# TempModule.net
KiCad netlist of a schematic drawn in EAGLE
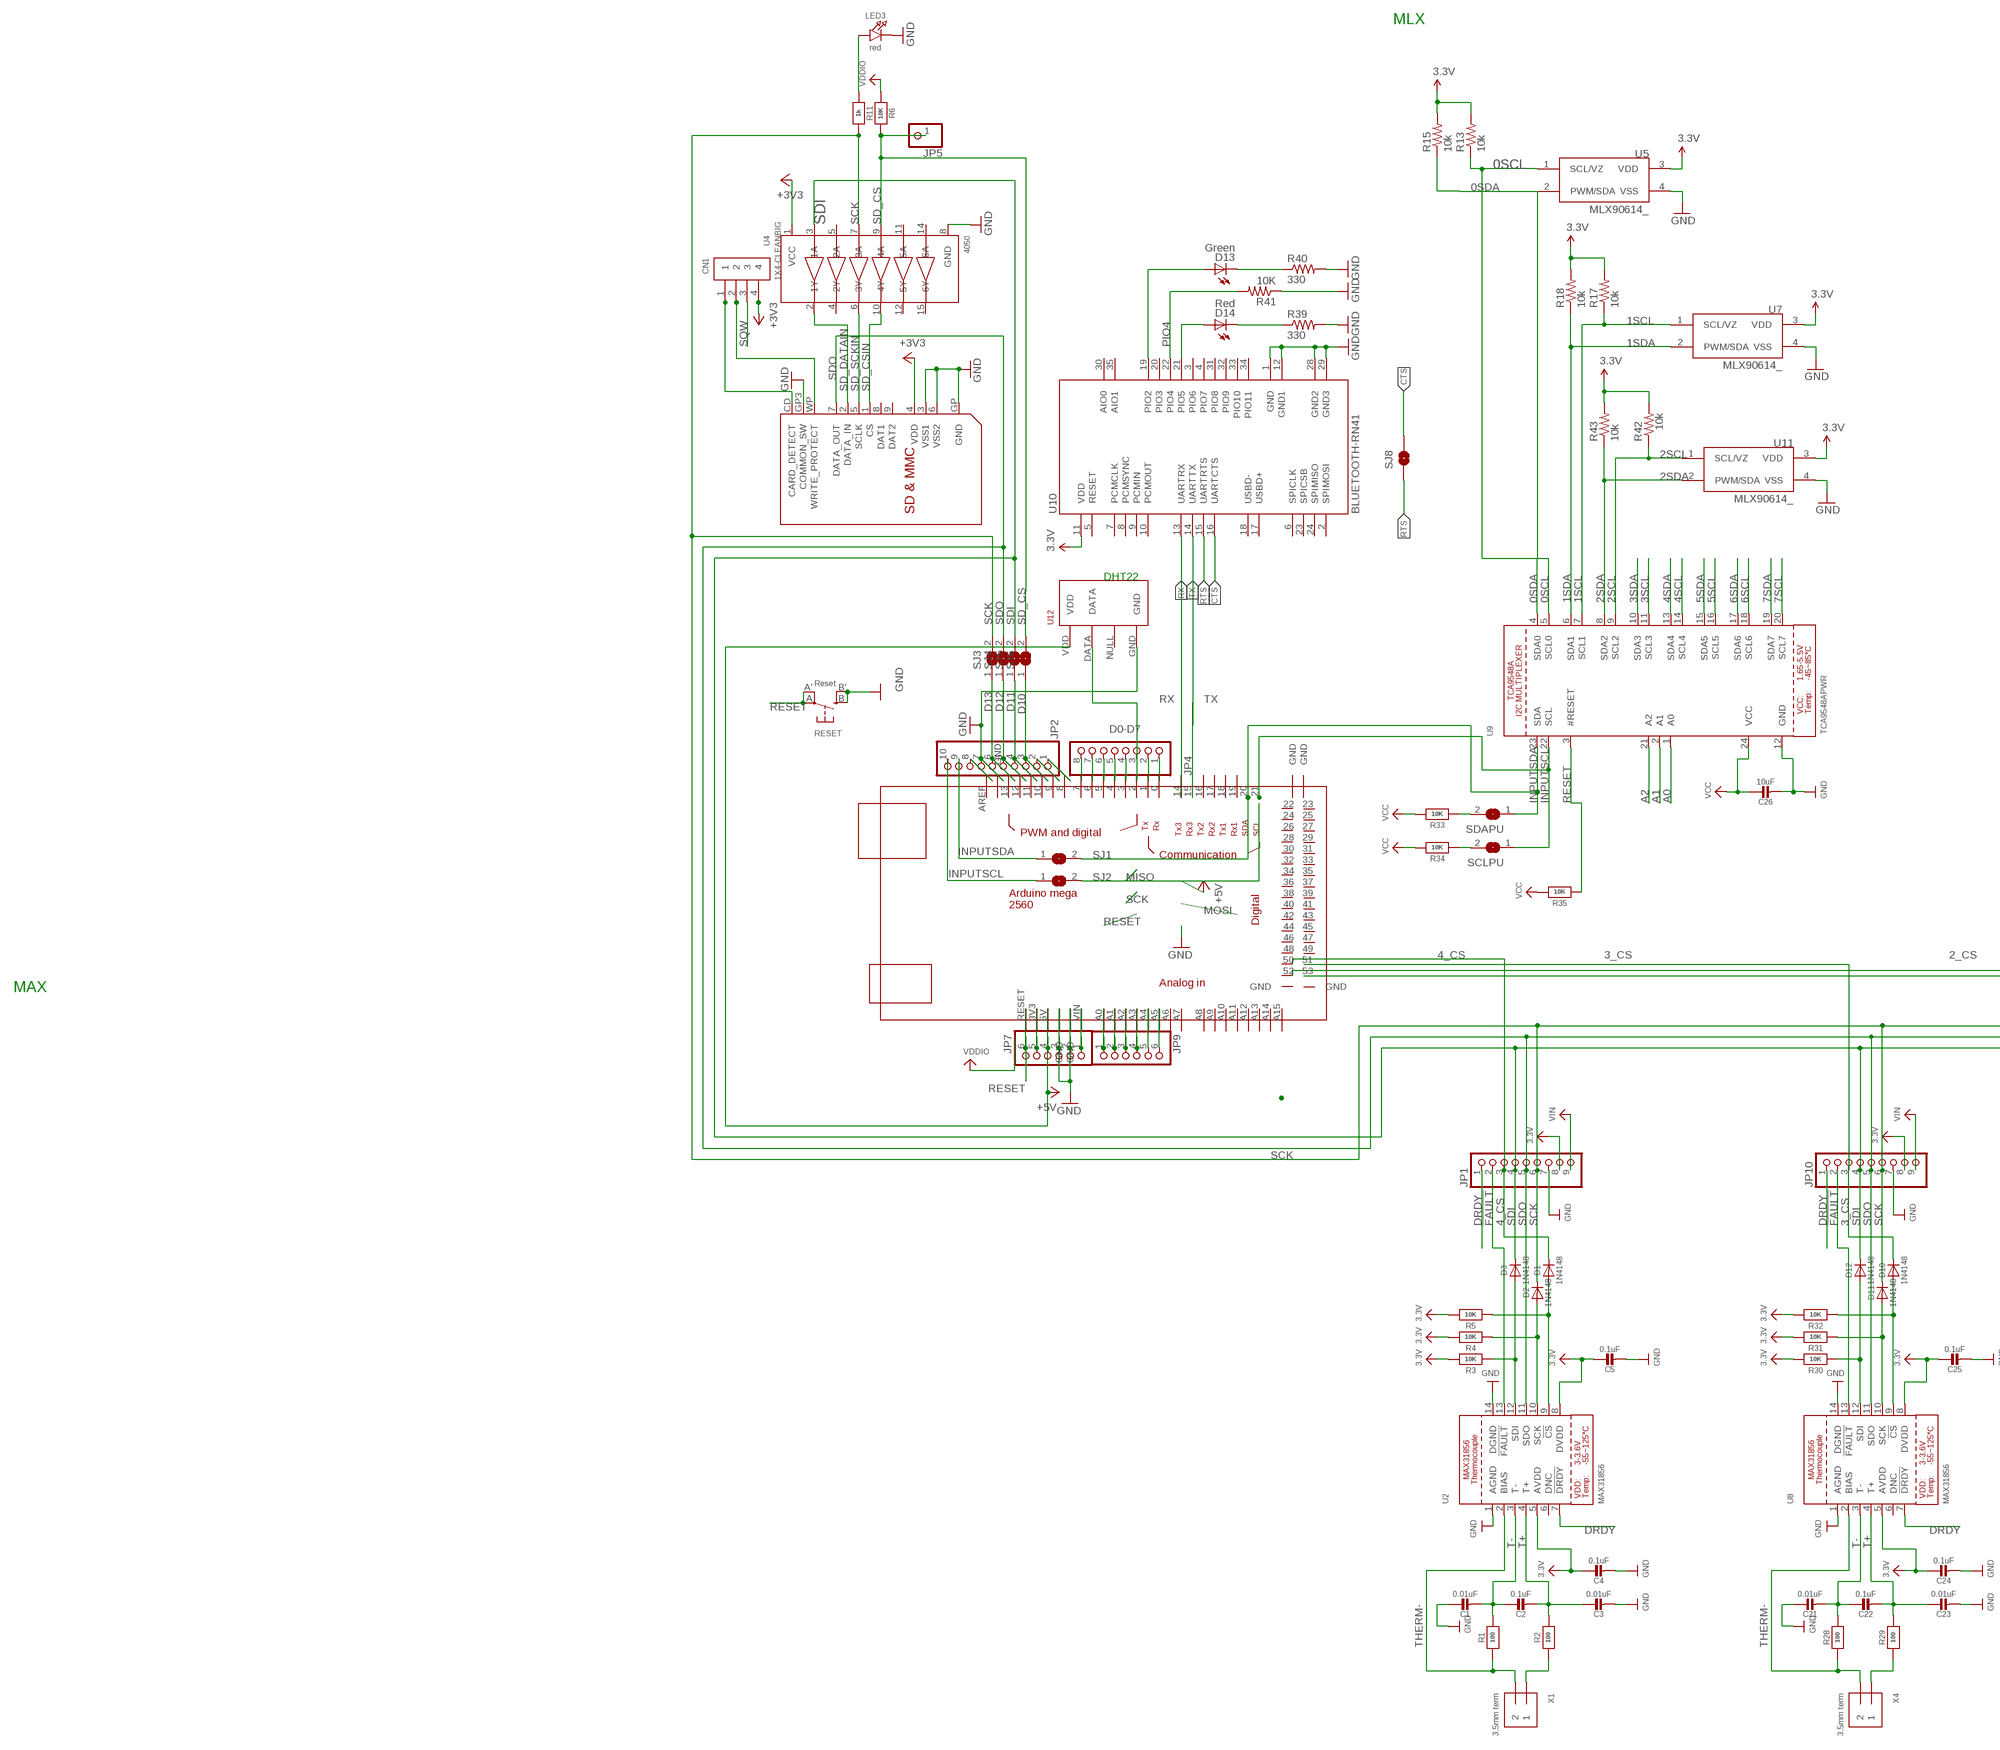
[diagram p0: schematic, sheet 1, part 1 of 2]
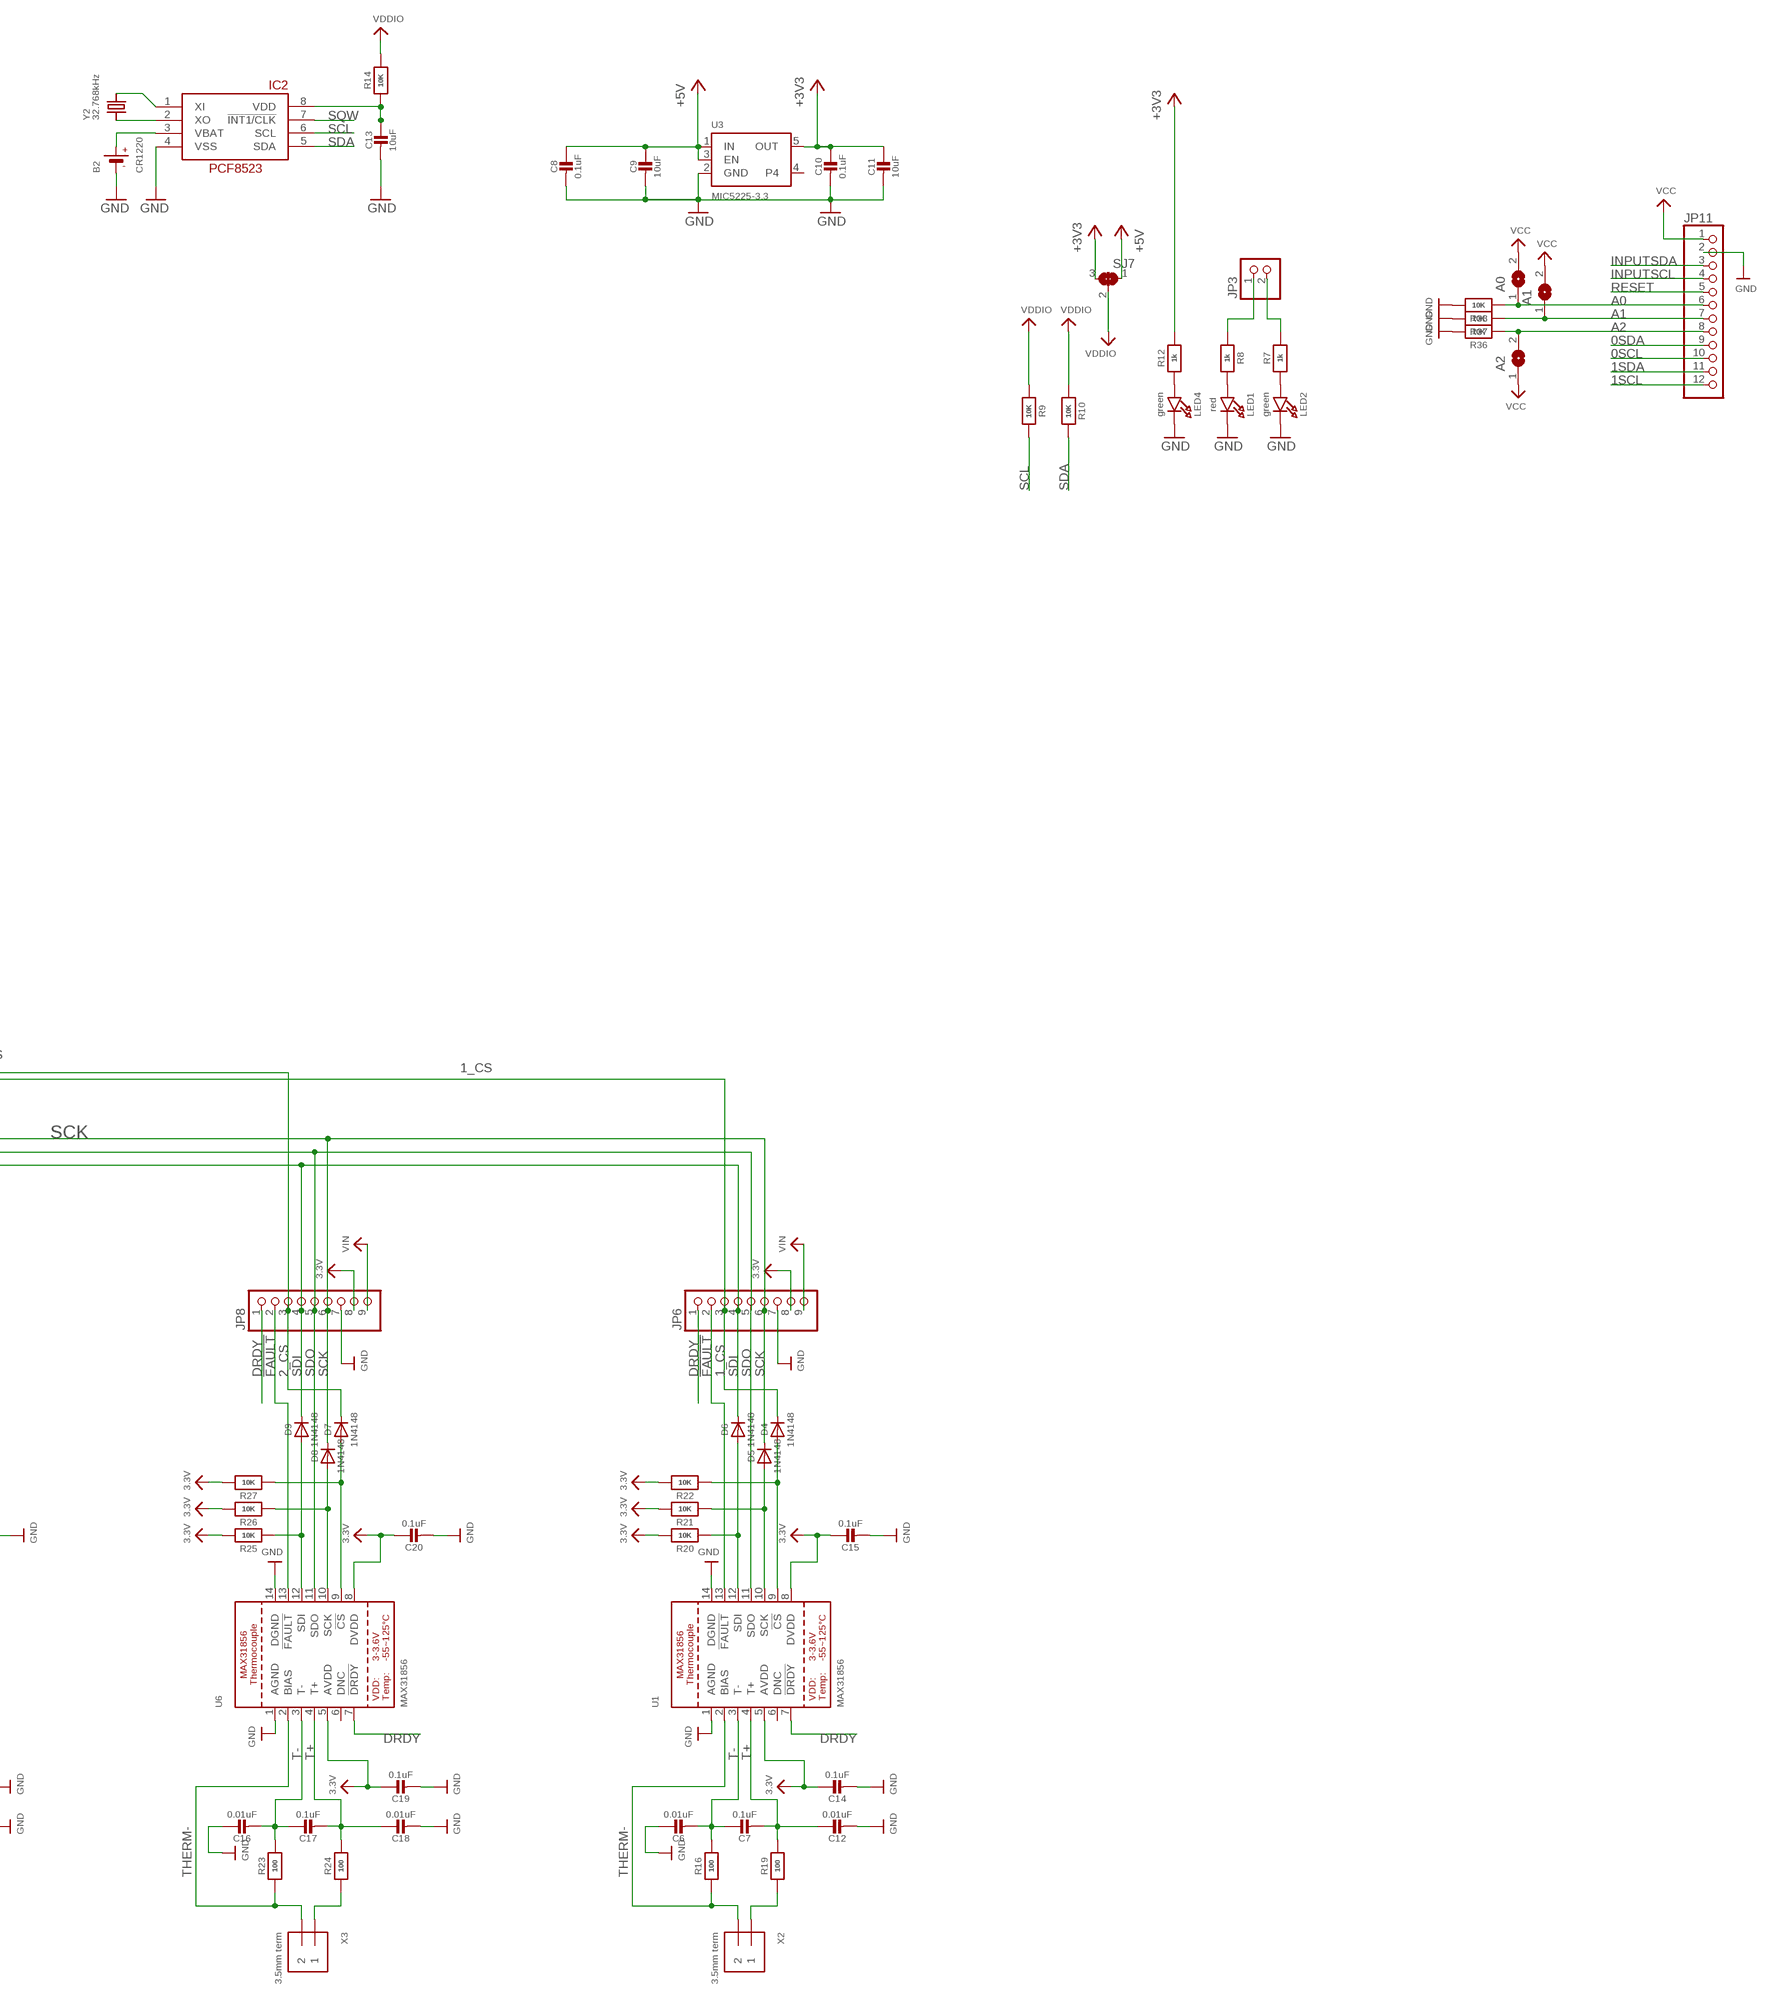
[diagram p1: schematic, sheet 1, part 2 of 2]

(export (version "E")
  (design (tool "Eeschema 10.0.6"))
  (components
    (comp (ref "A0")
      (value "SOLDERJUMPER")
      (footprint "eagle-import:SOLDERJUMPER_ARROW_NOPASTE")
      (libsource (lib "eagle-import") (part "SOLDERJUMPER"))
    )
    (comp (ref "A1")
      (value "SOLDERJUMPER")
      (footprint "eagle-import:SOLDERJUMPER_ARROW_NOPASTE")
      (libsource (lib "eagle-import") (part "SOLDERJUMPER"))
    )
    (comp (ref "A2")
      (value "SOLDERJUMPER")
      (footprint "eagle-import:SOLDERJUMPER_ARROW_NOPASTE")
      (libsource (lib "eagle-import") (part "SOLDERJUMPER"))
    )
    (comp (ref "B2")
      (value "CR1220")
      (footprint "eagle-import:CR1220")
      (libsource (lib "eagle-import") (part "BATTERYCR1220_SMT"))
    )
    (comp (ref "C1")
      (value "0.01uF")
      (footprint "eagle-import:0805_10MGAP")
      (libsource (lib "eagle-import") (part "CAP_CERAMIC0805_10MGAP"))
    )
    (comp (ref "C2")
      (value "0.1uF")
      (footprint "eagle-import:0805-NO")
      (libsource (lib "eagle-import") (part "CAP_CERAMIC0805-NOOUTLINE"))
    )
    (comp (ref "C3")
      (value "0.01uF")
      (footprint "eagle-import:0805-NO")
      (libsource (lib "eagle-import") (part "CAP_CERAMIC0805-NOOUTLINE"))
    )
    (comp (ref "C4")
      (value "0.1uF")
      (footprint "eagle-import:0805-NO")
      (libsource (lib "eagle-import") (part "CAP_CERAMIC0805-NOOUTLINE"))
    )
    (comp (ref "C5")
      (value "0.1uF")
      (footprint "eagle-import:0805-NO")
      (libsource (lib "eagle-import") (part "CAP_CERAMIC0805-NOOUTLINE"))
    )
    (comp (ref "C6")
      (value "0.01uF")
      (footprint "eagle-import:0805_10MGAP")
      (libsource (lib "eagle-import") (part "CAP_CERAMIC0805_10MGAP"))
    )
    (comp (ref "C7")
      (value "0.1uF")
      (footprint "eagle-import:0805-NO")
      (libsource (lib "eagle-import") (part "CAP_CERAMIC0805-NOOUTLINE"))
    )
    (comp (ref "C8")
      (value "0.1uF")
      (footprint "eagle-import:0805-NO")
      (libsource (lib "eagle-import") (part "CAP_CERAMIC0805-NOOUTLINE"))
    )
    (comp (ref "C9")
      (value "10uF")
      (footprint "eagle-import:0805-NO")
      (libsource (lib "eagle-import") (part "CAP_CERAMIC0805-NOOUTLINE"))
    )
    (comp (ref "C10")
      (value "0.1uF")
      (footprint "eagle-import:0805-NO")
      (libsource (lib "eagle-import") (part "CAP_CERAMIC0805-NOOUTLINE"))
    )
    (comp (ref "C11")
      (value "10uF")
      (footprint "eagle-import:0805-NO")
      (libsource (lib "eagle-import") (part "CAP_CERAMIC0805-NOOUTLINE"))
    )
    (comp (ref "C12")
      (value "0.01uF")
      (footprint "eagle-import:0805-NO")
      (libsource (lib "eagle-import") (part "CAP_CERAMIC0805-NOOUTLINE"))
    )
    (comp (ref "C13")
      (value "10uF")
      (footprint "eagle-import:0805-NO")
      (libsource (lib "eagle-import") (part "CAP_CERAMIC0805-NOOUTLINE"))
    )
    (comp (ref "C14")
      (value "0.1uF")
      (footprint "eagle-import:0805-NO")
      (libsource (lib "eagle-import") (part "CAP_CERAMIC0805-NOOUTLINE"))
    )
    (comp (ref "C15")
      (value "0.1uF")
      (footprint "eagle-import:0805-NO")
      (libsource (lib "eagle-import") (part "CAP_CERAMIC0805-NOOUTLINE"))
    )
    (comp (ref "C16")
      (value "0.01uF")
      (footprint "eagle-import:0805_10MGAP")
      (libsource (lib "eagle-import") (part "CAP_CERAMIC0805_10MGAP"))
    )
    (comp (ref "C17")
      (value "0.1uF")
      (footprint "eagle-import:0805-NO")
      (libsource (lib "eagle-import") (part "CAP_CERAMIC0805-NOOUTLINE"))
    )
    (comp (ref "C18")
      (value "0.01uF")
      (footprint "eagle-import:0805-NO")
      (libsource (lib "eagle-import") (part "CAP_CERAMIC0805-NOOUTLINE"))
    )
    (comp (ref "C19")
      (value "0.1uF")
      (footprint "eagle-import:0805-NO")
      (libsource (lib "eagle-import") (part "CAP_CERAMIC0805-NOOUTLINE"))
    )
    (comp (ref "C20")
      (value "0.1uF")
      (footprint "eagle-import:0805-NO")
      (libsource (lib "eagle-import") (part "CAP_CERAMIC0805-NOOUTLINE"))
    )
    (comp (ref "C21")
      (value "0.01uF")
      (footprint "eagle-import:0805_10MGAP")
      (libsource (lib "eagle-import") (part "CAP_CERAMIC0805_10MGAP"))
    )
    (comp (ref "C22")
      (value "0.1uF")
      (footprint "eagle-import:0805-NO")
      (libsource (lib "eagle-import") (part "CAP_CERAMIC0805-NOOUTLINE"))
    )
    (comp (ref "C23")
      (value "0.01uF")
      (footprint "eagle-import:0805-NO")
      (libsource (lib "eagle-import") (part "CAP_CERAMIC0805-NOOUTLINE"))
    )
    (comp (ref "C24")
      (value "0.1uF")
      (footprint "eagle-import:0805-NO")
      (libsource (lib "eagle-import") (part "CAP_CERAMIC0805-NOOUTLINE"))
    )
    (comp (ref "C25")
      (value "0.1uF")
      (footprint "eagle-import:0805-NO")
      (libsource (lib "eagle-import") (part "CAP_CERAMIC0805-NOOUTLINE"))
    )
    (comp (ref "C26")
      (value "10uF")
      (footprint "eagle-import:0805-NO")
      (libsource (lib "eagle-import") (part "CAP_CERAMIC0805-NOOUTLINE"))
    )
    (comp (ref "CN1")
      (value "1X4-CLEANBIG")
      (footprint "eagle-import:1X04-CLEANBIG")
      (libsource (lib "eagle-import") (part "1X4-CLEANBIG"))
    )
    (comp (ref "D1")
      (value "1N4148")
      (footprint "eagle-import:SOD-323")
      (libsource (lib "eagle-import") (part "DIODESOD-323"))
    )
    (comp (ref "D2")
      (value "1N4148")
      (footprint "eagle-import:SOD-323")
      (libsource (lib "eagle-import") (part "DIODESOD-323"))
    )
    (comp (ref "D3")
      (value "1N4148")
      (footprint "eagle-import:SOD-323")
      (libsource (lib "eagle-import") (part "DIODESOD-323"))
    )
    (comp (ref "D4")
      (value "1N4148")
      (footprint "eagle-import:SOD-323")
      (libsource (lib "eagle-import") (part "DIODESOD-323"))
    )
    (comp (ref "D5")
      (value "1N4148")
      (footprint "eagle-import:SOD-323")
      (libsource (lib "eagle-import") (part "DIODESOD-323"))
    )
    (comp (ref "D6")
      (value "1N4148")
      (footprint "eagle-import:SOD-323")
      (libsource (lib "eagle-import") (part "DIODESOD-323"))
    )
    (comp (ref "D7")
      (value "1N4148")
      (footprint "eagle-import:SOD-323")
      (libsource (lib "eagle-import") (part "DIODESOD-323"))
    )
    (comp (ref "D8")
      (value "1N4148")
      (footprint "eagle-import:SOD-323")
      (libsource (lib "eagle-import") (part "DIODESOD-323"))
    )
    (comp (ref "D9")
      (value "1N4148")
      (footprint "eagle-import:SOD-323")
      (libsource (lib "eagle-import") (part "DIODESOD-323"))
    )
    (comp (ref "D10")
      (value "1N4148")
      (footprint "eagle-import:SOD-323")
      (libsource (lib "eagle-import") (part "DIODESOD-323"))
    )
    (comp (ref "D11")
      (value "1N4148")
      (footprint "eagle-import:SOD-323")
      (libsource (lib "eagle-import") (part "DIODESOD-323"))
    )
    (comp (ref "D12")
      (value "1N4148")
      (footprint "eagle-import:SOD-323")
      (libsource (lib "eagle-import") (part "DIODESOD-323"))
    )
    (comp (ref "D13")
      (value "Green")
      (footprint "eagle-import:LED-0603")
      (libsource (lib "eagle-import") (part "LED0603"))
    )
    (comp (ref "D14")
      (value "Red")
      (footprint "eagle-import:LED-0603")
      (libsource (lib "eagle-import") (part "LED0603"))
    )
    (comp (ref "IC2")
      (value "PCF8523T")
      (footprint "eagle-import:SOIC8_150MIL")
      (libsource (lib "eagle-import") (part "RTC_PCF8523T"))
    )
    (comp (ref "JP1")
      (value "HEADER-1X970MIL")
      (footprint "eagle-import:1X09_ROUND_70")
      (libsource (lib "eagle-import") (part "HEADER-1X970MIL"))
    )
    (comp (ref "JP2")
      (value "HEADER-1X1070MIL")
      (footprint "eagle-import:1X10_ROUND70")
      (libsource (lib "eagle-import") (part "HEADER-1X1070MIL"))
    )
    (comp (ref "JP3")
      (value "HEADER-1X2ROUND")
      (footprint "eagle-import:1X02_ROUND")
      (libsource (lib "eagle-import") (part "HEADER-1X2ROUND"))
    )
    (comp (ref "JP4")
      (value "D0-D7")
      (footprint "eagle-import:1X08-BIG")
      (libsource (lib "eagle-import") (part "PINHD-1X8BIG"))
    )
    (comp (ref "JP5")
      (value "HEADER-1X1ROUND")
      (footprint "eagle-import:1X01_ROUND")
      (libsource (lib "eagle-import") (part "HEADER-1X1ROUND"))
    )
    (comp (ref "JP6")
      (value "HEADER-1X970MIL")
      (footprint "eagle-import:1X09_ROUND_70")
      (libsource (lib "eagle-import") (part "HEADER-1X970MIL"))
    )
    (comp (ref "JP7")
      (value "PINHD-1X6B")
      (footprint "eagle-import:1X06-BIG")
      (libsource (lib "eagle-import") (part "PINHD-1X6B"))
    )
    (comp (ref "JP8")
      (value "HEADER-1X970MIL")
      (footprint "eagle-import:1X09_ROUND_70")
      (libsource (lib "eagle-import") (part "HEADER-1X970MIL"))
    )
    (comp (ref "JP9")
      (value "PINHD-1X6B")
      (footprint "eagle-import:1X06-BIG")
      (libsource (lib "eagle-import") (part "PINHD-1X6B"))
    )
    (comp (ref "JP10")
      (value "HEADER-1X970MIL")
      (footprint "eagle-import:1X09_ROUND_70")
      (libsource (lib "eagle-import") (part "HEADER-1X970MIL"))
    )
    (comp (ref "JP11")
      (value "HEADER-1X12")
      (footprint "eagle-import:1X12_ROUND")
      (libsource (lib "eagle-import") (part "HEADER-1X12"))
    )
    (comp (ref "LED1")
      (value "red")
      (footprint "eagle-import:CHIPLED_0805_NOOUTLINE")
      (libsource (lib "eagle-import") (part "LED0805_NOOUTLINE"))
    )
    (comp (ref "LED2")
      (value "green")
      (footprint "eagle-import:CHIPLED_0805_NOOUTLINE")
      (libsource (lib "eagle-import") (part "LED0805_NOOUTLINE"))
    )
    (comp (ref "LED3")
      (value "red")
      (footprint "eagle-import:CHIPLED_0805_NOOUTLINE")
      (libsource (lib "eagle-import") (part "LED0805_NOOUTLINE"))
    )
    (comp (ref "LED4")
      (value "green")
      (footprint "eagle-import:CHIPLED_0805_NOOUTLINE")
      (libsource (lib "eagle-import") (part "LED0805_NOOUTLINE"))
    )
    (comp (ref "R1")
      (value "100")
      (footprint "eagle-import:0805-NO")
      (libsource (lib "eagle-import") (part "RESISTOR0805_NOOUTLINE"))
    )
    (comp (ref "R2")
      (value "100")
      (footprint "eagle-import:0805-NO")
      (libsource (lib "eagle-import") (part "RESISTOR0805_NOOUTLINE"))
    )
    (comp (ref "R3")
      (value "10K")
      (footprint "eagle-import:0805-NO")
      (libsource (lib "eagle-import") (part "RESISTOR0805_NOOUTLINE"))
    )
    (comp (ref "R4")
      (value "10K")
      (footprint "eagle-import:0805-NO")
      (libsource (lib "eagle-import") (part "RESISTOR0805_NOOUTLINE"))
    )
    (comp (ref "R5")
      (value "10K")
      (footprint "eagle-import:0805-NO")
      (libsource (lib "eagle-import") (part "RESISTOR0805_NOOUTLINE"))
    )
    (comp (ref "R6")
      (value "10K")
      (footprint "eagle-import:0805-NO")
      (libsource (lib "eagle-import") (part "RESISTOR0805_NOOUTLINE"))
    )
    (comp (ref "R7")
      (value "1k")
      (footprint "eagle-import:0805-NO")
      (libsource (lib "eagle-import") (part "RESISTOR0805_NOOUTLINE"))
    )
    (comp (ref "R8")
      (value "1k")
      (footprint "eagle-import:0805-NO")
      (libsource (lib "eagle-import") (part "RESISTOR0805_NOOUTLINE"))
    )
    (comp (ref "R9")
      (value "10K")
      (footprint "eagle-import:0805-NO")
      (libsource (lib "eagle-import") (part "RESISTOR0805_NOOUTLINE"))
    )
    (comp (ref "R10")
      (value "10K")
      (footprint "eagle-import:0805-NO")
      (libsource (lib "eagle-import") (part "RESISTOR0805_NOOUTLINE"))
    )
    (comp (ref "R11")
      (value "1k")
      (footprint "eagle-import:0805-NO")
      (libsource (lib "eagle-import") (part "RESISTOR0805_NOOUTLINE"))
    )
    (comp (ref "R12")
      (value "1k")
      (footprint "eagle-import:0805-NO")
      (libsource (lib "eagle-import") (part "RESISTOR0805_NOOUTLINE"))
    )
    (comp (ref "R13")
      (value "10k")
      (footprint "eagle-import:0402-RES")
      (libsource (lib "eagle-import") (part "RESISTOR0402-RES"))
    )
    (comp (ref "R14")
      (value "10K")
      (footprint "eagle-import:0805-NO")
      (libsource (lib "eagle-import") (part "RESISTOR0805_NOOUTLINE"))
    )
    (comp (ref "R15")
      (value "10k")
      (footprint "eagle-import:0402-RES")
      (libsource (lib "eagle-import") (part "RESISTOR0402-RES"))
    )
    (comp (ref "R16")
      (value "100")
      (footprint "eagle-import:0805-NO")
      (libsource (lib "eagle-import") (part "RESISTOR0805_NOOUTLINE"))
    )
    (comp (ref "R17")
      (value "10k")
      (footprint "eagle-import:0402-RES")
      (libsource (lib "eagle-import") (part "RESISTOR0402-RES"))
    )
    (comp (ref "R18")
      (value "10k")
      (footprint "eagle-import:0402-RES")
      (libsource (lib "eagle-import") (part "RESISTOR0402-RES"))
    )
    (comp (ref "R19")
      (value "100")
      (footprint "eagle-import:0805-NO")
      (libsource (lib "eagle-import") (part "RESISTOR0805_NOOUTLINE"))
    )
    (comp (ref "R20")
      (value "10K")
      (footprint "eagle-import:0805-NO")
      (libsource (lib "eagle-import") (part "RESISTOR0805_NOOUTLINE"))
    )
    (comp (ref "R21")
      (value "10K")
      (footprint "eagle-import:0805-NO")
      (libsource (lib "eagle-import") (part "RESISTOR0805_NOOUTLINE"))
    )
    (comp (ref "R22")
      (value "10K")
      (footprint "eagle-import:0805-NO")
      (libsource (lib "eagle-import") (part "RESISTOR0805_NOOUTLINE"))
    )
    (comp (ref "R23")
      (value "100")
      (footprint "eagle-import:0805-NO")
      (libsource (lib "eagle-import") (part "RESISTOR0805_NOOUTLINE"))
    )
    (comp (ref "R24")
      (value "100")
      (footprint "eagle-import:0805-NO")
      (libsource (lib "eagle-import") (part "RESISTOR0805_NOOUTLINE"))
    )
    (comp (ref "R25")
      (value "10K")
      (footprint "eagle-import:0805-NO")
      (libsource (lib "eagle-import") (part "RESISTOR0805_NOOUTLINE"))
    )
    (comp (ref "R26")
      (value "10K")
      (footprint "eagle-import:0805-NO")
      (libsource (lib "eagle-import") (part "RESISTOR0805_NOOUTLINE"))
    )
    (comp (ref "R27")
      (value "10K")
      (footprint "eagle-import:0805-NO")
      (libsource (lib "eagle-import") (part "RESISTOR0805_NOOUTLINE"))
    )
    (comp (ref "R28")
      (value "100")
      (footprint "eagle-import:0805-NO")
      (libsource (lib "eagle-import") (part "RESISTOR0805_NOOUTLINE"))
    )
    (comp (ref "R29")
      (value "100")
      (footprint "eagle-import:0805-NO")
      (libsource (lib "eagle-import") (part "RESISTOR0805_NOOUTLINE"))
    )
    (comp (ref "R30")
      (value "10K")
      (footprint "eagle-import:0805-NO")
      (libsource (lib "eagle-import") (part "RESISTOR0805_NOOUTLINE"))
    )
    (comp (ref "R31")
      (value "10K")
      (footprint "eagle-import:0805-NO")
      (libsource (lib "eagle-import") (part "RESISTOR0805_NOOUTLINE"))
    )
    (comp (ref "R32")
      (value "10K")
      (footprint "eagle-import:0805-NO")
      (libsource (lib "eagle-import") (part "RESISTOR0805_NOOUTLINE"))
    )
    (comp (ref "R33")
      (value "10K")
      (footprint "eagle-import:0805-NO")
      (libsource (lib "eagle-import") (part "RESISTOR0805_NOOUTLINE"))
    )
    (comp (ref "R34")
      (value "10K")
      (footprint "eagle-import:0805-NO")
      (libsource (lib "eagle-import") (part "RESISTOR0805_NOOUTLINE"))
    )
    (comp (ref "R35")
      (value "10K")
      (footprint "eagle-import:_0805MP")
      (libsource (lib "eagle-import") (part "RESISTOR_0805MP"))
    )
    (comp (ref "R36")
      (value "10K")
      (footprint "eagle-import:0805-NO")
      (libsource (lib "eagle-import") (part "RESISTOR0805_NOOUTLINE"))
    )
    (comp (ref "R37")
      (value "10K")
      (footprint "eagle-import:0805-NO")
      (libsource (lib "eagle-import") (part "RESISTOR0805_NOOUTLINE"))
    )
    (comp (ref "R38")
      (value "10K")
      (footprint "eagle-import:0805-NO")
      (libsource (lib "eagle-import") (part "RESISTOR0805_NOOUTLINE"))
    )
    (comp (ref "R39")
      (value "330")
      (footprint "eagle-import:0603-RES")
      (libsource (lib "eagle-import") (part "RESISTOR0603-RES"))
    )
    (comp (ref "R40")
      (value "330")
      (footprint "eagle-import:0603-RES")
      (libsource (lib "eagle-import") (part "RESISTOR0603-RES"))
    )
    (comp (ref "R41")
      (value "10K")
      (footprint "eagle-import:0603-RES")
      (libsource (lib "eagle-import") (part "RESISTOR0603-RES"))
    )
    (comp (ref "R42")
      (value "10k")
      (footprint "eagle-import:0402-RES")
      (libsource (lib "eagle-import") (part "RESISTOR0402-RES"))
    )
    (comp (ref "R43")
      (value "10k")
      (footprint "eagle-import:0402-RES")
      (libsource (lib "eagle-import") (part "RESISTOR0402-RES"))
    )
    (comp (ref "RESET")
      (value "Reset")
      (footprint "eagle-import:EVQ-Q2_SMALLER")
      (libsource (lib "eagle-import") (part "SWITCH_TACT_SMT_EVQQ2_SMALL"))
    )
    (comp (ref "SCLPU")
      (value "SOLDERJUMPERCLOSED")
      (footprint "eagle-import:SOLDERJUMPER_CLOSEDWIRE")
      (libsource (lib "eagle-import") (part "SOLDERJUMPERCLOSED"))
    )
    (comp (ref "SDAPU")
      (value "SOLDERJUMPERCLOSED")
      (footprint "eagle-import:SOLDERJUMPER_CLOSEDWIRE")
      (libsource (lib "eagle-import") (part "SOLDERJUMPERCLOSED"))
    )
    (comp (ref "SJ1")
      (value "SOLDERJUMPER")
      (footprint "eagle-import:SOLDERJUMPER_ARROW_NOPASTE")
      (libsource (lib "eagle-import") (part "SOLDERJUMPER"))
    )
    (comp (ref "SJ2")
      (value "SOLDERJUMPER")
      (footprint "eagle-import:SOLDERJUMPER_ARROW_NOPASTE")
      (libsource (lib "eagle-import") (part "SOLDERJUMPER"))
    )
    (comp (ref "SJ3")
      (value "SOLDERJUMPER")
      (footprint "eagle-import:SOLDERJUMPER_ARROW_NOPASTE")
      (libsource (lib "eagle-import") (part "SOLDERJUMPER"))
    )
    (comp (ref "SJ4")
      (value "SOLDERJUMPER")
      (footprint "eagle-import:SOLDERJUMPER_ARROW_NOPASTE")
      (libsource (lib "eagle-import") (part "SOLDERJUMPER"))
    )
    (comp (ref "SJ5")
      (value "SOLDERJUMPER")
      (footprint "eagle-import:SOLDERJUMPER_ARROW_NOPASTE")
      (libsource (lib "eagle-import") (part "SOLDERJUMPER"))
    )
    (comp (ref "SJ6")
      (value "SOLDERJUMPERCLOSED")
      (footprint "eagle-import:SOLDERJUMPER_CLOSEDWIRE")
      (libsource (lib "eagle-import") (part "SOLDERJUMPERCLOSED"))
    )
    (comp (ref "SJ7")
      (value "SOLDERJUMPER_2WAY")
      (footprint "eagle-import:SOLDERJUMPER_2WAY_OPEN_NOPASTE")
      (libsource (lib "eagle-import") (part "SOLDERJUMPER_2WAY"))
    )
    (comp (ref "SJ8")
      (value "SOLDERJUMPERNO")
      (footprint "eagle-import:SJ_2S-NO")
      (libsource (lib "eagle-import") (part "SOLDERJUMPERNO"))
    )
    (comp (ref "U$1")
      (value "MEGA_DEVICE")
      (footprint "eagle-import:MEGAOUTLINE")
      (libsource (lib "eagle-import") (part "MEGA_DEVICE"))
    )
    (comp (ref "U$14")
      (value "SDMMC06132")
      (footprint "eagle-import:06132")
      (libsource (lib "eagle-import") (part "SDMMC06132"))
    )
    (comp (ref "U1")
      (value "MAX31856")
      (footprint "eagle-import:TSSOP14")
      (libsource (lib "eagle-import") (part "MAX31856"))
    )
    (comp (ref "U2")
      (value "MAX31856")
      (footprint "eagle-import:TSSOP14")
      (libsource (lib "eagle-import") (part "MAX31856"))
    )
    (comp (ref "U3")
      (value "MIC5225-3.3")
      (footprint "eagle-import:SOT23-5")
      (libsource (lib "eagle-import") (part "VREG_SOT23-5"))
    )
    (comp (ref "U4")
      (value "4050")
      (footprint "eagle-import:SOIC16")
      (libsource (lib "eagle-import") (part "74HC4050D"))
    )
    (comp (ref "U5")
      (value "MLX90614_")
      (footprint "eagle-import:TO-39")
      (libsource (lib "eagle-import") (part "MLX90614_"))
    )
    (comp (ref "U6")
      (value "MAX31856")
      (footprint "eagle-import:TSSOP14")
      (libsource (lib "eagle-import") (part "MAX31856"))
    )
    (comp (ref "U7")
      (value "MLX90614_")
      (footprint "eagle-import:TO-39")
      (libsource (lib "eagle-import") (part "MLX90614_"))
    )
    (comp (ref "U8")
      (value "MAX31856")
      (footprint "eagle-import:TSSOP14")
      (libsource (lib "eagle-import") (part "MAX31856"))
    )
    (comp (ref "U9")
      (value "TCA9548APWR")
      (footprint "eagle-import:TSSOP24")
      (libsource (lib "eagle-import") (part "TCA9548A"))
    )
    (comp (ref "U10")
      (value "BLUETOOTH-RN41")
      (footprint "eagle-import:RN41")
      (libsource (lib "eagle-import") (part "BLUETOOTH-RN41{dblquote}"))
    )
    (comp (ref "U11")
      (value "MLX90614_")
      (footprint "eagle-import:TO-39")
      (libsource (lib "eagle-import") (part "MLX90614_"))
    )
    (comp (ref "U12")
      (value "RHT03_DHT-22_AM2302")
      (footprint "eagle-import:RHT03_DHT-22")
      (libsource (lib "eagle-import") (part "RHT03_DHT-22_AM2302"))
    )
    (comp (ref "X1")
      (value "3.5mm term")
      (footprint "eagle-import:TERMBLOCK_1X2-3.5MM")
      (libsource (lib "eagle-import") (part "TERMBLOCK_1X2"))
    )
    (comp (ref "X2")
      (value "3.5mm term")
      (footprint "eagle-import:TERMBLOCK_1X2-3.5MM")
      (libsource (lib "eagle-import") (part "TERMBLOCK_1X2"))
    )
    (comp (ref "X3")
      (value "3.5mm term")
      (footprint "eagle-import:TERMBLOCK_1X2-3.5MM")
      (libsource (lib "eagle-import") (part "TERMBLOCK_1X2"))
    )
    (comp (ref "X4")
      (value "3.5mm term")
      (footprint "eagle-import:TERMBLOCK_1X2-3.5MM")
      (libsource (lib "eagle-import") (part "TERMBLOCK_1X2"))
    )
    (comp (ref "Y2")
      (value "32.768kHz")
      (footprint "eagle-import:CRYSTAL_8X3.8")
      (libsource (lib "eagle-import") (part "CRYSTAL8.0X3.8"))
    )
  )
  (nets
    (net (code "1") (name "+3V3") (class "Default")
      (node (ref "C10") (pin "1") (pinfunction "1_1") (pintype "passive"))
      (node (ref "C11") (pin "1") (pinfunction "1_1") (pintype "passive"))
      (node (ref "CN1") (pin "4") (pinfunction "4_4") (pintype "bidirectional"))
      (node (ref "R12") (pin "2") (pinfunction "2_2") (pintype "passive"))
      (node (ref "SJ7") (pin "3") (pinfunction "3_3") (pintype "passive"))
      (node (ref "U$14") (pin "4") (pinfunction "VDD_4") (pintype "power_in"))
      (node (ref "U3") (pin "5") (pinfunction "OUT_5") (pintype "power_in"))
      (node (ref "U4") (pin "1") (pinfunction "VCC_1") (pintype "bidirectional"))
    )
    (net (code "2") (name "+5V") (class "Default")
      (node (ref "C8") (pin "1") (pinfunction "1_1") (pintype "passive"))
      (node (ref "C9") (pin "1") (pinfunction "1_1") (pintype "passive"))
      (node (ref "JP7") (pin "4") (pinfunction "4_4") (pintype "passive"))
      (node (ref "SJ7") (pin "1") (pinfunction "1_1") (pintype "passive"))
      (node (ref "U$1") (pin "5V") (pinfunction "5V_5V") (pintype "bidirectional"))
      (node (ref "U12") (pin "VDD") (pinfunction "VDD_VDD") (pintype "power_in"))
      (node (ref "U3") (pin "1") (pinfunction "IN_1") (pintype "power_in"))
      (node (ref "U3") (pin "3") (pinfunction "EN_3") (pintype "input"))
    )
    (net (code "3") (name "/0SCL") (class "Default")
      (node (ref "JP11") (pin "10") (pinfunction "10_10") (pintype "passive"))
      (node (ref "R13") (pin "1") (pinfunction "1_1") (pintype "passive"))
      (node (ref "U5") (pin "1") (pinfunction "SCL/VZ_1") (pintype "bidirectional"))
      (node (ref "U9") (pin "5") (pinfunction "SCL0_5") (pintype "bidirectional"))
    )
    (net (code "4") (name "/0SDA") (class "Default")
      (node (ref "JP11") (pin "9") (pinfunction "9_9") (pintype "passive"))
      (node (ref "R15") (pin "1") (pinfunction "1_1") (pintype "passive"))
      (node (ref "U5") (pin "2") (pinfunction "PWM/SDA_2") (pintype "bidirectional"))
      (node (ref "U9") (pin "4") (pinfunction "SDA0_4") (pintype "bidirectional"))
    )
    (net (code "5") (name "/1SCL") (class "Default")
      (node (ref "JP11") (pin "12") (pinfunction "12_12") (pintype "passive"))
      (node (ref "R17") (pin "1") (pinfunction "1_1") (pintype "passive"))
      (node (ref "U7") (pin "1") (pinfunction "SCL/VZ_1") (pintype "bidirectional"))
      (node (ref "U9") (pin "7") (pinfunction "SCL1_7") (pintype "bidirectional"))
    )
    (net (code "6") (name "/1SDA") (class "Default")
      (node (ref "JP11") (pin "11") (pinfunction "11_11") (pintype "passive"))
      (node (ref "R18") (pin "1") (pinfunction "1_1") (pintype "passive"))
      (node (ref "U7") (pin "2") (pinfunction "PWM/SDA_2") (pintype "bidirectional"))
      (node (ref "U9") (pin "6") (pinfunction "SDA1_6") (pintype "bidirectional"))
    )
    (net (code "7") (name "/1_CS") (class "Default")
      (node (ref "D4") (pin "C") (pinfunction "C_C") (pintype "passive"))
      (node (ref "JP6") (pin "3") (pinfunction "3_3") (pintype "passive"))
      (node (ref "U$1") (pin "53") (pinfunction "53_53") (pintype "bidirectional"))
    )
    (net (code "8") (name "/2SCL") (class "Default")
      (node (ref "R42") (pin "1") (pinfunction "1_1") (pintype "passive"))
      (node (ref "U11") (pin "1") (pinfunction "SCL/VZ_1") (pintype "bidirectional"))
      (node (ref "U9") (pin "9") (pinfunction "SCL2_9") (pintype "bidirectional"))
    )
    (net (code "9") (name "/2SDA") (class "Default")
      (node (ref "R43") (pin "1") (pinfunction "1_1") (pintype "passive"))
      (node (ref "U11") (pin "2") (pinfunction "PWM/SDA_2") (pintype "bidirectional"))
      (node (ref "U9") (pin "8") (pinfunction "SDA2_8") (pintype "bidirectional"))
    )
    (net (code "10") (name "/2_CS") (class "Default")
      (node (ref "D7") (pin "C") (pinfunction "C_C") (pintype "passive"))
      (node (ref "JP8") (pin "3") (pinfunction "3_3") (pintype "passive"))
      (node (ref "U$1") (pin "52") (pinfunction "52_52") (pintype "bidirectional"))
    )
    (net (code "11") (name "/3SCL") (class "Default")
      (node (ref "U9") (pin "11") (pinfunction "SCL3_11") (pintype "bidirectional"))
    )
    (net (code "12") (name "/3SDA") (class "Default")
      (node (ref "U9") (pin "10") (pinfunction "SDA3_10") (pintype "bidirectional"))
    )
    (net (code "13") (name "/3_CS") (class "Default")
      (node (ref "D10") (pin "C") (pinfunction "C_C") (pintype "passive"))
      (node (ref "JP10") (pin "3") (pinfunction "3_3") (pintype "passive"))
      (node (ref "U$1") (pin "51") (pinfunction "51_51") (pintype "bidirectional"))
    )
    (net (code "14") (name "/4SCL") (class "Default")
      (node (ref "U9") (pin "14") (pinfunction "SCL4_14") (pintype "bidirectional"))
    )
    (net (code "15") (name "/4SDA") (class "Default")
      (node (ref "U9") (pin "13") (pinfunction "SDA4_13") (pintype "bidirectional"))
    )
    (net (code "16") (name "/4_CS") (class "Default")
      (node (ref "D1") (pin "C") (pinfunction "C_C") (pintype "passive"))
      (node (ref "JP1") (pin "3") (pinfunction "3_3") (pintype "passive"))
      (node (ref "U$1") (pin "50") (pinfunction "50_50") (pintype "bidirectional"))
    )
    (net (code "17") (name "/5SCL") (class "Default")
      (node (ref "U9") (pin "16") (pinfunction "SCL5_16") (pintype "bidirectional"))
    )
    (net (code "18") (name "/5SDA") (class "Default")
      (node (ref "U9") (pin "15") (pinfunction "SDA5_15") (pintype "bidirectional"))
    )
    (net (code "19") (name "/6SCL") (class "Default")
      (node (ref "U9") (pin "18") (pinfunction "SCL6_18") (pintype "bidirectional"))
    )
    (net (code "20") (name "/6SDA") (class "Default")
      (node (ref "U9") (pin "17") (pinfunction "SDA6_17") (pintype "bidirectional"))
    )
    (net (code "21") (name "/7SCL") (class "Default")
      (node (ref "U9") (pin "20") (pinfunction "SCL7_20") (pintype "bidirectional"))
    )
    (net (code "22") (name "/7SDA") (class "Default")
      (node (ref "U9") (pin "19") (pinfunction "SDA7_19") (pintype "bidirectional"))
    )
    (net (code "23") (name "/A0") (class "Default")
      (node (ref "A0") (pin "1") (pinfunction "1_1") (pintype "passive"))
      (node (ref "JP11") (pin "6") (pinfunction "6_6") (pintype "passive"))
      (node (ref "R38") (pin "1") (pinfunction "1_1") (pintype "passive"))
      (node (ref "U9") (pin "1") (pinfunction "A0_1") (pintype "bidirectional"))
    )
    (net (code "24") (name "/A1") (class "Default")
      (node (ref "A1") (pin "1") (pinfunction "1_1") (pintype "passive"))
      (node (ref "JP11") (pin "7") (pinfunction "7_7") (pintype "passive"))
      (node (ref "R37") (pin "1") (pinfunction "1_1") (pintype "passive"))
      (node (ref "U9") (pin "2") (pinfunction "A1_2") (pintype "bidirectional"))
    )
    (net (code "25") (name "/A2") (class "Default")
      (node (ref "A2") (pin "2") (pinfunction "2_2") (pintype "passive"))
      (node (ref "JP11") (pin "8") (pinfunction "8_8") (pintype "passive"))
      (node (ref "R36") (pin "1") (pinfunction "1_1") (pintype "passive"))
      (node (ref "U9") (pin "21") (pinfunction "A2_21") (pintype "bidirectional"))
    )
    (net (code "26") (name "/A5") (class "Default")
      (node (ref "JP9") (pin "6") (pinfunction "6_6") (pintype "passive"))
      (node (ref "SJ2") (pin "2") (pinfunction "2_2") (pintype "passive"))
      (node (ref "U$1") (pin "A5") (pinfunction "A5_A5") (pintype "bidirectional"))
    )
    (net (code "27") (name "/D10") (class "Default")
      (node (ref "JP2") (pin "3") (pinfunction "3_3") (pintype "passive"))
      (node (ref "SJ6") (pin "1") (pinfunction "1_1") (pintype "passive"))
    )
    (net (code "28") (name "/D11") (class "Default")
      (node (ref "JP2") (pin "4") (pinfunction "4_4") (pintype "passive"))
      (node (ref "SJ5") (pin "1") (pinfunction "1_1") (pintype "passive"))
    )
    (net (code "29") (name "/D12") (class "Default")
      (node (ref "JP2") (pin "5") (pinfunction "5_5") (pintype "passive"))
      (node (ref "SJ4") (pin "1") (pinfunction "1_1") (pintype "passive"))
    )
    (net (code "30") (name "/D13") (class "Default")
      (node (ref "JP2") (pin "6") (pinfunction "6_6") (pintype "passive"))
      (node (ref "SJ3") (pin "1") (pinfunction "1_1") (pintype "passive"))
    )
    (net (code "31") (name "/DRDY") (class "Default")
      (node (ref "JP1") (pin "1") (pinfunction "1_1") (pintype "passive"))
      (node (ref "JP10") (pin "1") (pinfunction "1_1") (pintype "passive"))
      (node (ref "JP6") (pin "1") (pinfunction "1_1") (pintype "passive"))
      (node (ref "JP8") (pin "1") (pinfunction "1_1") (pintype "passive"))
      (node (ref "U1") (pin "7") (pinfunction "~{DRDY}_7") (pintype "output"))
      (node (ref "U2") (pin "7") (pinfunction "~{DRDY}_7") (pintype "output"))
      (node (ref "U6") (pin "7") (pinfunction "~{DRDY}_7") (pintype "output"))
      (node (ref "U8") (pin "7") (pinfunction "~{DRDY}_7") (pintype "output"))
    )
    (net (code "32") (name "/INPUTSCL") (class "Default")
      (node (ref "JP11") (pin "4") (pinfunction "4_4") (pintype "passive"))
      (node (ref "JP2") (pin "10") (pinfunction "10_10") (pintype "passive"))
      (node (ref "SCLPU") (pin "1") (pinfunction "1_1") (pintype "passive"))
      (node (ref "SJ2") (pin "1") (pinfunction "1_1") (pintype "passive"))
      (node (ref "U$1") (pin "21") (pinfunction "21_21") (pintype "bidirectional"))
      (node (ref "U9") (pin "22") (pinfunction "SCL_22") (pintype "bidirectional"))
    )
    (net (code "33") (name "/INPUTSDA") (class "Default")
      (node (ref "JP11") (pin "3") (pinfunction "3_3") (pintype "passive"))
      (node (ref "JP2") (pin "9") (pinfunction "9_9") (pintype "passive"))
      (node (ref "SDAPU") (pin "1") (pinfunction "1_1") (pintype "passive"))
      (node (ref "SJ1") (pin "1") (pinfunction "1_1") (pintype "passive"))
      (node (ref "SJ1") (pin "2") (pinfunction "2_2") (pintype "passive"))
      (node (ref "U$1") (pin "20") (pinfunction "20_20") (pintype "bidirectional"))
      (node (ref "U9") (pin "23") (pinfunction "SDA_23") (pintype "bidirectional"))
    )
    (net (code "36") (name "/PIO4") (class "Default")
      (node (ref "R41") (pin "2") (pinfunction "2_2") (pintype "passive"))
      (node (ref "U10") (pin "22") (pinfunction "PIO4_22") (pintype "bidirectional"))
    )
    (net (code "37") (name "/RESET") (class "Default")
      (node (ref "JP11") (pin "5") (pinfunction "5_5") (pintype "passive"))
      (node (ref "JP7") (pin "6") (pinfunction "6_6") (pintype "passive"))
      (node (ref "R35") (pin "1") (pinfunction "1_1") (pintype "passive"))
      (node (ref "RESET") (pin "A") (pinfunction "P_A") (pintype "passive"))
      (node (ref "RESET") (pin "A'") (pinfunction "P1_A'") (pintype "passive"))
      (node (ref "U$1") (pin "RESET") (pinfunction "RESET_RESET") (pintype "bidirectional"))
      (node (ref "U9") (pin "3") (pinfunction "#RESET_3") (pintype "bidirectional"))
    )
    (net (code "38") (name "/SCK") (class "Default")
      (node (ref "D11") (pin "C") (pinfunction "C_C") (pintype "passive"))
      (node (ref "D2") (pin "C") (pinfunction "C_C") (pintype "passive"))
      (node (ref "D5") (pin "C") (pinfunction "C_C") (pintype "passive"))
      (node (ref "D8") (pin "C") (pinfunction "C_C") (pintype "passive"))
      (node (ref "JP1") (pin "6") (pinfunction "6_6") (pintype "passive"))
      (node (ref "JP10") (pin "6") (pinfunction "6_6") (pintype "passive"))
      (node (ref "JP6") (pin "6") (pinfunction "6_6") (pintype "passive"))
      (node (ref "JP8") (pin "6") (pinfunction "6_6") (pintype "passive"))
      (node (ref "R11") (pin "2") (pinfunction "2_2") (pintype "passive"))
      (node (ref "SJ3") (pin "2") (pinfunction "2_2") (pintype "passive"))
      (node (ref "U4") (pin "7") (pinfunction "3A_7") (pintype "bidirectional"))
    )
    (net (code "39") (name "/SCL") (class "Default")
      (node (ref "IC2") (pin "6") (pinfunction "SCL_6") (pintype "bidirectional"))
      (node (ref "R9") (pin "2") (pinfunction "2_2") (pintype "passive"))
    )
    (net (code "40") (name "/SDA") (class "Default")
      (node (ref "IC2") (pin "5") (pinfunction "SDA_5") (pintype "bidirectional"))
      (node (ref "R10") (pin "2") (pinfunction "2_2") (pintype "passive"))
    )
    (net (code "41") (name "/SDI") (class "Default")
      (node (ref "D12") (pin "C") (pinfunction "C_C") (pintype "passive"))
      (node (ref "D3") (pin "C") (pinfunction "C_C") (pintype "passive"))
      (node (ref "D6") (pin "C") (pinfunction "C_C") (pintype "passive"))
      (node (ref "D9") (pin "C") (pinfunction "C_C") (pintype "passive"))
      (node (ref "JP1") (pin "4") (pinfunction "4_4") (pintype "passive"))
      (node (ref "JP10") (pin "4") (pinfunction "4_4") (pintype "passive"))
      (node (ref "JP6") (pin "4") (pinfunction "4_4") (pintype "passive"))
      (node (ref "JP8") (pin "4") (pinfunction "4_4") (pintype "passive"))
      (node (ref "SJ5") (pin "2") (pinfunction "2_2") (pintype "passive"))
      (node (ref "U4") (pin "3") (pinfunction "1A_3") (pintype "bidirectional"))
    )
    (net (code "42") (name "/SDO") (class "Default")
      (node (ref "JP1") (pin "5") (pinfunction "5_5") (pintype "passive"))
      (node (ref "JP10") (pin "5") (pinfunction "5_5") (pintype "passive"))
      (node (ref "JP6") (pin "5") (pinfunction "5_5") (pintype "passive"))
      (node (ref "JP8") (pin "5") (pinfunction "5_5") (pintype "passive"))
      (node (ref "SJ4") (pin "2") (pinfunction "2_2") (pintype "passive"))
      (node (ref "U$14") (pin "7") (pinfunction "DATA_OUT_7") (pintype "output"))
      (node (ref "U1") (pin "11") (pinfunction "SDO_11") (pintype "output"))
      (node (ref "U2") (pin "11") (pinfunction "SDO_11") (pintype "output"))
      (node (ref "U6") (pin "11") (pinfunction "SDO_11") (pintype "output"))
      (node (ref "U8") (pin "11") (pinfunction "SDO_11") (pintype "output"))
    )
    (net (code "43") (name "/SD_CS") (class "Default")
      (node (ref "JP5") (pin "1") (pinfunction "1_1") (pintype "passive"))
      (node (ref "R6") (pin "2") (pinfunction "2_2") (pintype "passive"))
      (node (ref "SJ6") (pin "2") (pinfunction "2_2") (pintype "passive"))
      (node (ref "U4") (pin "9") (pinfunction "4A_9") (pintype "bidirectional"))
    )
    (net (code "44") (name "/SD_CSIN") (class "Default")
      (node (ref "U$14") (pin "1") (pinfunction "CS_1") (pintype "input"))
      (node (ref "U4") (pin "10") (pinfunction "4Y_10") (pintype "bidirectional"))
    )
    (net (code "45") (name "/SD_DATAIN") (class "Default")
      (node (ref "U$14") (pin "2") (pinfunction "DATA_IN_2") (pintype "input"))
      (node (ref "U4") (pin "2") (pinfunction "1Y_2") (pintype "bidirectional"))
    )
    (net (code "46") (name "/SD_SCKIN") (class "Default")
      (node (ref "U$14") (pin "5") (pinfunction "SCLK_5") (pintype "input"))
      (node (ref "U4") (pin "6") (pinfunction "3Y_6") (pintype "bidirectional"))
    )
    (net (code "47") (name "/SQW") (class "Default")
      (node (ref "CN1") (pin "3") (pinfunction "3_3") (pintype "bidirectional"))
      (node (ref "IC2") (pin "7") (pinfunction "~{INT1/CLK}_7") (pintype "output"))
    )
    (net (code "48") (name "/T+") (class "Default")
      (node (ref "C12") (pin "1") (pinfunction "1_1") (pintype "passive"))
      (node (ref "C17") (pin "2") (pinfunction "2_2") (pintype "passive"))
      (node (ref "C18") (pin "1") (pinfunction "1_1") (pintype "passive"))
      (node (ref "C2") (pin "2") (pinfunction "2_2") (pintype "passive"))
      (node (ref "C22") (pin "2") (pinfunction "2_2") (pintype "passive"))
      (node (ref "C23") (pin "1") (pinfunction "1_1") (pintype "passive"))
      (node (ref "C3") (pin "1") (pinfunction "1_1") (pintype "passive"))
      (node (ref "C7") (pin "2") (pinfunction "2_2") (pintype "passive"))
      (node (ref "R19") (pin "2") (pinfunction "2_2") (pintype "passive"))
      (node (ref "R2") (pin "2") (pinfunction "2_2") (pintype "passive"))
      (node (ref "R24") (pin "2") (pinfunction "2_2") (pintype "passive"))
      (node (ref "R29") (pin "2") (pinfunction "2_2") (pintype "passive"))
      (node (ref "U1") (pin "4") (pinfunction "T+_4") (pintype "input"))
      (node (ref "U2") (pin "4") (pinfunction "T+_4") (pintype "input"))
      (node (ref "U6") (pin "4") (pinfunction "T+_4") (pintype "input"))
      (node (ref "U8") (pin "4") (pinfunction "T+_4") (pintype "input"))
    )
    (net (code "49") (name "/T-") (class "Default")
      (node (ref "C1") (pin "2") (pinfunction "2_2") (pintype "passive"))
      (node (ref "C16") (pin "2") (pinfunction "2_2") (pintype "passive"))
      (node (ref "C17") (pin "1") (pinfunction "1_1") (pintype "passive"))
      (node (ref "C2") (pin "1") (pinfunction "1_1") (pintype "passive"))
      (node (ref "C21") (pin "2") (pinfunction "2_2") (pintype "passive"))
      (node (ref "C22") (pin "1") (pinfunction "1_1") (pintype "passive"))
      (node (ref "C6") (pin "2") (pinfunction "2_2") (pintype "passive"))
      (node (ref "C7") (pin "1") (pinfunction "1_1") (pintype "passive"))
      (node (ref "R1") (pin "2") (pinfunction "2_2") (pintype "passive"))
      (node (ref "R16") (pin "2") (pinfunction "2_2") (pintype "passive"))
      (node (ref "R23") (pin "2") (pinfunction "2_2") (pintype "passive"))
      (node (ref "R28") (pin "2") (pinfunction "2_2") (pintype "passive"))
      (node (ref "U1") (pin "3") (pinfunction "T-_3") (pintype "input"))
      (node (ref "U2") (pin "3") (pinfunction "T-_3") (pintype "input"))
      (node (ref "U6") (pin "3") (pinfunction "T-_3") (pintype "input"))
      (node (ref "U8") (pin "3") (pinfunction "T-_3") (pintype "input"))
    )
    (net (code "50") (name "/THERM-") (class "Default")
      (node (ref "R1") (pin "1") (pinfunction "1_1") (pintype "passive"))
      (node (ref "R16") (pin "1") (pinfunction "1_1") (pintype "passive"))
      (node (ref "R23") (pin "1") (pinfunction "1_1") (pintype "passive"))
      (node (ref "R28") (pin "1") (pinfunction "1_1") (pintype "passive"))
      (node (ref "U1") (pin "2") (pinfunction "BIAS_2") (pintype "power_in"))
      (node (ref "U2") (pin "2") (pinfunction "BIAS_2") (pintype "power_in"))
      (node (ref "U6") (pin "2") (pinfunction "BIAS_2") (pintype "power_in"))
      (node (ref "U8") (pin "2") (pinfunction "BIAS_2") (pintype "power_in"))
      (node (ref "X1") (pin "2") (pinfunction "2_2") (pintype "passive"))
      (node (ref "X2") (pin "2") (pinfunction "2_2") (pintype "passive"))
      (node (ref "X3") (pin "2") (pinfunction "2_2") (pintype "passive"))
      (node (ref "X4") (pin "2") (pinfunction "2_2") (pintype "passive"))
    )
    (net (code "51") (name "/~{FAULT}") (class "Default")
      (node (ref "JP1") (pin "2") (pinfunction "2_2") (pintype "passive"))
      (node (ref "JP10") (pin "2") (pinfunction "2_2") (pintype "passive"))
      (node (ref "JP6") (pin "2") (pinfunction "2_2") (pintype "passive"))
      (node (ref "JP8") (pin "2") (pinfunction "2_2") (pintype "passive"))
      (node (ref "U1") (pin "13") (pinfunction "~{FAULT}_13") (pintype "output"))
      (node (ref "U2") (pin "13") (pinfunction "~{FAULT}_13") (pintype "output"))
      (node (ref "U6") (pin "13") (pinfunction "~{FAULT}_13") (pintype "output"))
      (node (ref "U8") (pin "13") (pinfunction "~{FAULT}_13") (pintype "output"))
    )
    (net (code "52") (name "3.3V") (class "Default")
      (node (ref "C14") (pin "1") (pinfunction "1_1") (pintype "passive"))
      (node (ref "C15") (pin "1") (pinfunction "1_1") (pintype "passive"))
      (node (ref "C19") (pin "1") (pinfunction "1_1") (pintype "passive"))
      (node (ref "C20") (pin "1") (pinfunction "1_1") (pintype "passive"))
      (node (ref "C24") (pin "1") (pinfunction "1_1") (pintype "passive"))
      (node (ref "C25") (pin "1") (pinfunction "1_1") (pintype "passive"))
      (node (ref "C4") (pin "1") (pinfunction "1_1") (pintype "passive"))
      (node (ref "C5") (pin "1") (pinfunction "1_1") (pintype "passive"))
      (node (ref "JP1") (pin "8") (pinfunction "8_8") (pintype "passive"))
      (node (ref "JP10") (pin "8") (pinfunction "8_8") (pintype "passive"))
      (node (ref "JP6") (pin "8") (pinfunction "8_8") (pintype "passive"))
      (node (ref "JP8") (pin "8") (pinfunction "8_8") (pintype "passive"))
      (node (ref "R13") (pin "2") (pinfunction "2_2") (pintype "passive"))
      (node (ref "R15") (pin "2") (pinfunction "2_2") (pintype "passive"))
      (node (ref "R17") (pin "2") (pinfunction "2_2") (pintype "passive"))
      (node (ref "R18") (pin "2") (pinfunction "2_2") (pintype "passive"))
      (node (ref "R20") (pin "2") (pinfunction "2_2") (pintype "passive"))
      (node (ref "R21") (pin "2") (pinfunction "2_2") (pintype "passive"))
      (node (ref "R22") (pin "2") (pinfunction "2_2") (pintype "passive"))
      (node (ref "R25") (pin "2") (pinfunction "2_2") (pintype "passive"))
      (node (ref "R26") (pin "2") (pinfunction "2_2") (pintype "passive"))
      (node (ref "R27") (pin "2") (pinfunction "2_2") (pintype "passive"))
      (node (ref "R3") (pin "2") (pinfunction "2_2") (pintype "passive"))
      (node (ref "R30") (pin "2") (pinfunction "2_2") (pintype "passive"))
      (node (ref "R31") (pin "2") (pinfunction "2_2") (pintype "passive"))
      (node (ref "R32") (pin "2") (pinfunction "2_2") (pintype "passive"))
      (node (ref "R4") (pin "2") (pinfunction "2_2") (pintype "passive"))
      (node (ref "R42") (pin "2") (pinfunction "2_2") (pintype "passive"))
      (node (ref "R43") (pin "2") (pinfunction "2_2") (pintype "passive"))
      (node (ref "R5") (pin "2") (pinfunction "2_2") (pintype "passive"))
      (node (ref "U1") (pin "5") (pinfunction "AVDD_5") (pintype "power_in"))
      (node (ref "U1") (pin "8") (pinfunction "DVDD_8") (pintype "power_in"))
      (node (ref "U10") (pin "11") (pinfunction "VDD_11") (pintype "bidirectional"))
      (node (ref "U11") (pin "3") (pinfunction "VDD_3") (pintype "bidirectional"))
      (node (ref "U2") (pin "5") (pinfunction "AVDD_5") (pintype "power_in"))
      (node (ref "U2") (pin "8") (pinfunction "DVDD_8") (pintype "power_in"))
      (node (ref "U5") (pin "3") (pinfunction "VDD_3") (pintype "bidirectional"))
      (node (ref "U6") (pin "5") (pinfunction "AVDD_5") (pintype "power_in"))
      (node (ref "U6") (pin "8") (pinfunction "DVDD_8") (pintype "power_in"))
      (node (ref "U7") (pin "3") (pinfunction "VDD_3") (pintype "bidirectional"))
      (node (ref "U8") (pin "5") (pinfunction "AVDD_5") (pintype "power_in"))
      (node (ref "U8") (pin "8") (pinfunction "DVDD_8") (pintype "power_in"))
    )
    (net (code "53") (name "CTS") (class "Default")
      (node (ref "SJ8") (pin "2") (pinfunction "2_2") (pintype "passive"))
      (node (ref "U10") (pin "16") (pinfunction "UARTCTS_16") (pintype "bidirectional"))
    )
    (net (code "54") (name "GND") (class "Default")
      (node (ref "B2") (pin "-") (pinfunction "-_-") (pintype "passive"))
      (node (ref "C1") (pin "1") (pinfunction "1_1") (pintype "passive"))
      (node (ref "C10") (pin "2") (pinfunction "2_2") (pintype "passive"))
      (node (ref "C11") (pin "2") (pinfunction "2_2") (pintype "passive"))
      (node (ref "C12") (pin "2") (pinfunction "2_2") (pintype "passive"))
      (node (ref "C13") (pin "2") (pinfunction "2_2") (pintype "passive"))
      (node (ref "C14") (pin "2") (pinfunction "2_2") (pintype "passive"))
      (node (ref "C15") (pin "2") (pinfunction "2_2") (pintype "passive"))
      (node (ref "C16") (pin "1") (pinfunction "1_1") (pintype "passive"))
      (node (ref "C18") (pin "2") (pinfunction "2_2") (pintype "passive"))
      (node (ref "C19") (pin "2") (pinfunction "2_2") (pintype "passive"))
      (node (ref "C20") (pin "2") (pinfunction "2_2") (pintype "passive"))
      (node (ref "C21") (pin "1") (pinfunction "1_1") (pintype "passive"))
      (node (ref "C23") (pin "2") (pinfunction "2_2") (pintype "passive"))
      (node (ref "C24") (pin "2") (pinfunction "2_2") (pintype "passive"))
      (node (ref "C25") (pin "2") (pinfunction "2_2") (pintype "passive"))
      (node (ref "C26") (pin "2") (pinfunction "2_2") (pintype "passive"))
      (node (ref "C3") (pin "2") (pinfunction "2_2") (pintype "passive"))
      (node (ref "C4") (pin "2") (pinfunction "2_2") (pintype "passive"))
      (node (ref "C5") (pin "2") (pinfunction "2_2") (pintype "passive"))
      (node (ref "C6") (pin "1") (pinfunction "1_1") (pintype "passive"))
      (node (ref "C8") (pin "2") (pinfunction "2_2") (pintype "passive"))
      (node (ref "C9") (pin "2") (pinfunction "2_2") (pintype "passive"))
      (node (ref "IC2") (pin "4") (pinfunction "VSS_4") (pintype "power_in"))
      (node (ref "JP1") (pin "7") (pinfunction "7_7") (pintype "passive"))
      (node (ref "JP10") (pin "7") (pinfunction "7_7") (pintype "passive"))
      (node (ref "JP11") (pin "2") (pinfunction "2_2") (pintype "passive"))
      (node (ref "JP2") (pin "7") (pinfunction "7_7") (pintype "passive"))
      (node (ref "JP6") (pin "7") (pinfunction "7_7") (pintype "passive"))
      (node (ref "JP7") (pin "2") (pinfunction "2_2") (pintype "passive"))
      (node (ref "JP7") (pin "3") (pinfunction "3_3") (pintype "passive"))
      (node (ref "JP8") (pin "7") (pinfunction "7_7") (pintype "passive"))
      (node (ref "LED1") (pin "C") (pinfunction "C_C") (pintype "passive"))
      (node (ref "LED2") (pin "C") (pinfunction "C_C") (pintype "passive"))
      (node (ref "LED3") (pin "C") (pinfunction "C_C") (pintype "passive"))
      (node (ref "LED4") (pin "C") (pinfunction "C_C") (pintype "passive"))
      (node (ref "R36") (pin "2") (pinfunction "2_2") (pintype "passive"))
      (node (ref "R37") (pin "2") (pinfunction "2_2") (pintype "passive"))
      (node (ref "R38") (pin "2") (pinfunction "2_2") (pintype "passive"))
      (node (ref "R39") (pin "2") (pinfunction "2_2") (pintype "passive"))
      (node (ref "R40") (pin "2") (pinfunction "2_2") (pintype "passive"))
      (node (ref "R41") (pin "1") (pinfunction "1_1") (pintype "passive"))
      (node (ref "RESET") (pin "B") (pinfunction "S_B") (pintype "passive"))
      (node (ref "RESET") (pin "B'") (pinfunction "S1_B'") (pintype "passive"))
      (node (ref "U$1") (pin "GND@2") (pinfunction "GND_GND@2") (pintype "bidirectional"))
      (node (ref "U$1") (pin "GND@3") (pinfunction "GND_GND@3") (pintype "bidirectional"))
      (node (ref "U$14") (pin "3") (pinfunction "VSS1_3") (pintype "power_in"))
      (node (ref "U$14") (pin "6") (pinfunction "VSS2_6") (pintype "power_in"))
      (node (ref "U$14") (pin "GP") (pinfunction "GND_GP") (pintype "power_in"))
      (node (ref "U$14") (pin "GP3") (pinfunction "COMMON_SW_GP3") (pintype "passive"))
      (node (ref "U1") (pin "1") (pinfunction "AGND_1") (pintype "power_in"))
      (node (ref "U1") (pin "14") (pinfunction "DGND_14") (pintype "power_in"))
      (node (ref "U10") (pin "1") (pinfunction "GND_1") (pintype "bidirectional"))
      (node (ref "U10") (pin "12") (pinfunction "GND1_12") (pintype "bidirectional"))
      (node (ref "U10") (pin "28") (pinfunction "GND2_28") (pintype "bidirectional"))
      (node (ref "U10") (pin "29") (pinfunction "GND3_29") (pintype "bidirectional"))
      (node (ref "U11") (pin "4") (pinfunction "VSS_4") (pintype "bidirectional"))
      (node (ref "U12") (pin "GND") (pinfunction "GND_GND") (pintype "power_in"))
      (node (ref "U2") (pin "1") (pinfunction "AGND_1") (pintype "power_in"))
      (node (ref "U2") (pin "14") (pinfunction "DGND_14") (pintype "power_in"))
      (node (ref "U3") (pin "2") (pinfunction "GND_2") (pintype "power_in"))
      (node (ref "U4") (pin "8") (pinfunction "GND_8") (pintype "bidirectional"))
      (node (ref "U5") (pin "4") (pinfunction "VSS_4") (pintype "bidirectional"))
      (node (ref "U6") (pin "1") (pinfunction "AGND_1") (pintype "power_in"))
      (node (ref "U6") (pin "14") (pinfunction "DGND_14") (pintype "power_in"))
      (node (ref "U7") (pin "4") (pinfunction "VSS_4") (pintype "bidirectional"))
      (node (ref "U8") (pin "1") (pinfunction "AGND_1") (pintype "power_in"))
      (node (ref "U8") (pin "14") (pinfunction "DGND_14") (pintype "power_in"))
      (node (ref "U9") (pin "12") (pinfunction "GND_12") (pintype "bidirectional"))
    )
    (net (code "55") (name "Net-(D13-PadC)") (class "Default")
      (node (ref "D13") (pin "C") (pinfunction "C_C") (pintype "passive"))
      (node (ref "R40") (pin "1") (pinfunction "1_1") (pintype "passive"))
    )
    (net (code "56") (name "Net-(D14-PadC)") (class "Default")
      (node (ref "D14") (pin "C") (pinfunction "C_C") (pintype "passive"))
      (node (ref "R39") (pin "1") (pinfunction "1_1") (pintype "passive"))
    )
    (net (code "57") (name "Net-(IC2-VBAT)") (class "Default")
      (node (ref "B2") (pin "+$1") (pinfunction "+_+$1") (pintype "passive"))
      (node (ref "B2") (pin "+$2") (pinfunction "+_+$2") (pintype "passive"))
      (node (ref "IC2") (pin "3") (pinfunction "VBAT_3") (pintype "power_in"))
    )
    (net (code "58") (name "Net-(IC2-VDD)") (class "Default")
      (node (ref "C13") (pin "1") (pinfunction "1_1") (pintype "passive"))
      (node (ref "IC2") (pin "8") (pinfunction "VDD_8") (pintype "power_in"))
      (node (ref "R14") (pin "1") (pinfunction "1_1") (pintype "passive"))
    )
    (net (code "59") (name "Net-(IC2-XI)") (class "Default")
      (node (ref "IC2") (pin "1") (pinfunction "XI_1") (pintype "input"))
      (node (ref "Y2") (pin "P$4") (pinfunction "2_P$4") (pintype "passive"))
    )
    (net (code "60") (name "Net-(IC2-XO)") (class "Default")
      (node (ref "IC2") (pin "2") (pinfunction "XO_2") (pintype "output"))
      (node (ref "Y2") (pin "P$1") (pinfunction "1_P$1") (pintype "passive"))
    )
    (net (code "61") (name "Net-(JP3-Pad1)") (class "Default")
      (node (ref "JP3") (pin "1") (pinfunction "1_1") (pintype "passive"))
      (node (ref "R8") (pin "1") (pinfunction "1_1") (pintype "passive"))
    )
    (net (code "62") (name "Net-(JP3-Pad2)") (class "Default")
      (node (ref "JP3") (pin "2") (pinfunction "2_2") (pintype "passive"))
      (node (ref "R7") (pin "2") (pinfunction "2_2") (pintype "passive"))
    )
    (net (code "63") (name "Net-(JP4-Pad3)") (class "Default")
      (node (ref "JP4") (pin "3") (pinfunction "3_3") (pintype "passive"))
      (node (ref "U12") (pin "DATA") (pinfunction "DATA_DATA") (pintype "bidirectional"))
    )
    (net (code "64") (name "Net-(JP7-Pad1)") (class "Default")
      (node (ref "JP7") (pin "1") (pinfunction "1_1") (pintype "passive"))
      (node (ref "U$1") (pin "VIN") (pinfunction "VIN_VIN") (pintype "bidirectional"))
    )
    (net (code "65") (name "Net-(JP7-Pad5)") (class "Default")
      (node (ref "JP7") (pin "5") (pinfunction "5_5") (pintype "passive"))
      (node (ref "U$1") (pin "3V3") (pinfunction "3V3_3V3") (pintype "bidirectional"))
    )
    (net (code "66") (name "Net-(JP9-Pad1)") (class "Default")
      (node (ref "JP9") (pin "1") (pinfunction "1_1") (pintype "passive"))
      (node (ref "U$1") (pin "A0") (pinfunction "A0_A0") (pintype "bidirectional"))
    )
    (net (code "67") (name "Net-(JP9-Pad2)") (class "Default")
      (node (ref "JP9") (pin "2") (pinfunction "2_2") (pintype "passive"))
      (node (ref "U$1") (pin "A1") (pinfunction "A1_A1") (pintype "bidirectional"))
    )
    (net (code "68") (name "Net-(JP9-Pad3)") (class "Default")
      (node (ref "JP9") (pin "3") (pinfunction "3_3") (pintype "passive"))
      (node (ref "U$1") (pin "A2") (pinfunction "A2_A2") (pintype "bidirectional"))
    )
    (net (code "69") (name "Net-(JP9-Pad4)") (class "Default")
      (node (ref "JP9") (pin "4") (pinfunction "4_4") (pintype "passive"))
      (node (ref "U$1") (pin "A3") (pinfunction "A3_A3") (pintype "bidirectional"))
    )
    (net (code "70") (name "Net-(JP9-Pad5)") (class "Default")
      (node (ref "JP9") (pin "5") (pinfunction "5_5") (pintype "passive"))
      (node (ref "U$1") (pin "A4") (pinfunction "A4_A4") (pintype "bidirectional"))
    )
    (net (code "71") (name "Net-(LED1-PadA)") (class "Default")
      (node (ref "LED1") (pin "A") (pinfunction "A_A") (pintype "passive"))
      (node (ref "R8") (pin "2") (pinfunction "2_2") (pintype "passive"))
    )
    (net (code "72") (name "Net-(LED2-PadA)") (class "Default")
      (node (ref "LED2") (pin "A") (pinfunction "A_A") (pintype "passive"))
      (node (ref "R7") (pin "1") (pinfunction "1_1") (pintype "passive"))
    )
    (net (code "73") (name "Net-(LED3-PadA)") (class "Default")
      (node (ref "LED3") (pin "A") (pinfunction "A_A") (pintype "passive"))
      (node (ref "R11") (pin "1") (pinfunction "1_1") (pintype "passive"))
    )
    (net (code "74") (name "Net-(LED4-PadA)") (class "Default")
      (node (ref "LED4") (pin "A") (pinfunction "A_A") (pintype "passive"))
      (node (ref "R12") (pin "1") (pinfunction "1_1") (pintype "passive"))
    )
    (net (code "75") (name "Net-(R2-Pad1)") (class "Default")
      (node (ref "R2") (pin "1") (pinfunction "1_1") (pintype "passive"))
      (node (ref "X1") (pin "1") (pinfunction "1_1") (pintype "passive"))
    )
    (net (code "76") (name "Net-(R19-Pad1)") (class "Default")
      (node (ref "R19") (pin "1") (pinfunction "1_1") (pintype "passive"))
      (node (ref "X2") (pin "1") (pinfunction "1_1") (pintype "passive"))
    )
    (net (code "77") (name "Net-(R24-Pad1)") (class "Default")
      (node (ref "R24") (pin "1") (pinfunction "1_1") (pintype "passive"))
      (node (ref "X3") (pin "1") (pinfunction "1_1") (pintype "passive"))
    )
    (net (code "78") (name "Net-(R29-Pad1)") (class "Default")
      (node (ref "R29") (pin "1") (pinfunction "1_1") (pintype "passive"))
      (node (ref "X4") (pin "1") (pinfunction "1_1") (pintype "passive"))
    )
    (net (code "79") (name "Net-(R33-Pad1)") (class "Default")
      (node (ref "R33") (pin "1") (pinfunction "1_1") (pintype "passive"))
      (node (ref "SDAPU") (pin "2") (pinfunction "2_2") (pintype "passive"))
    )
    (net (code "80") (name "Net-(R34-Pad1)") (class "Default")
      (node (ref "R34") (pin "1") (pinfunction "1_1") (pintype "passive"))
      (node (ref "SCLPU") (pin "2") (pinfunction "2_2") (pintype "passive"))
    )
    (net (code "81") (name "Net-(U$14-CARD_DETECT)") (class "Default")
      (node (ref "CN1") (pin "1") (pinfunction "1_1") (pintype "bidirectional"))
      (node (ref "U$14") (pin "CD") (pinfunction "CARD_DETECT_CD") (pintype "passive"))
    )
    (net (code "82") (name "Net-(U$14-WRITE_PROTECT)") (class "Default")
      (node (ref "CN1") (pin "2") (pinfunction "2_2") (pintype "bidirectional"))
      (node (ref "U$14") (pin "WP") (pinfunction "WRITE_PROTECT_WP") (pintype "passive"))
    )
    (net (code "83") (name "Net-(U1-SCK)") (class "Default")
      (node (ref "D5") (pin "A") (pinfunction "A_A") (pintype "passive"))
      (node (ref "R21") (pin "1") (pinfunction "1_1") (pintype "passive"))
      (node (ref "U1") (pin "10") (pinfunction "SCK_10") (pintype "input"))
    )
    (net (code "84") (name "Net-(U1-SDI)") (class "Default")
      (node (ref "D6") (pin "A") (pinfunction "A_A") (pintype "passive"))
      (node (ref "R20") (pin "1") (pinfunction "1_1") (pintype "passive"))
      (node (ref "U1") (pin "12") (pinfunction "SDI_12") (pintype "input"))
    )
    (net (code "85") (name "Net-(U1-~{CS})") (class "Default")
      (node (ref "D4") (pin "A") (pinfunction "A_A") (pintype "passive"))
      (node (ref "R22") (pin "1") (pinfunction "1_1") (pintype "passive"))
      (node (ref "U1") (pin "9") (pinfunction "~{CS}_9") (pintype "input"))
    )
    (net (code "86") (name "Net-(U2-SCK)") (class "Default")
      (node (ref "D2") (pin "A") (pinfunction "A_A") (pintype "passive"))
      (node (ref "R4") (pin "1") (pinfunction "1_1") (pintype "passive"))
      (node (ref "U2") (pin "10") (pinfunction "SCK_10") (pintype "input"))
    )
    (net (code "87") (name "Net-(U2-SDI)") (class "Default")
      (node (ref "D3") (pin "A") (pinfunction "A_A") (pintype "passive"))
      (node (ref "R3") (pin "1") (pinfunction "1_1") (pintype "passive"))
      (node (ref "U2") (pin "12") (pinfunction "SDI_12") (pintype "input"))
    )
    (net (code "88") (name "Net-(U2-~{CS})") (class "Default")
      (node (ref "D1") (pin "A") (pinfunction "A_A") (pintype "passive"))
      (node (ref "R5") (pin "1") (pinfunction "1_1") (pintype "passive"))
      (node (ref "U2") (pin "9") (pinfunction "~{CS}_9") (pintype "input"))
    )
    (net (code "89") (name "Net-(U6-SCK)") (class "Default")
      (node (ref "D8") (pin "A") (pinfunction "A_A") (pintype "passive"))
      (node (ref "R26") (pin "1") (pinfunction "1_1") (pintype "passive"))
      (node (ref "U6") (pin "10") (pinfunction "SCK_10") (pintype "input"))
    )
    (net (code "90") (name "Net-(U6-SDI)") (class "Default")
      (node (ref "D9") (pin "A") (pinfunction "A_A") (pintype "passive"))
      (node (ref "R25") (pin "1") (pinfunction "1_1") (pintype "passive"))
      (node (ref "U6") (pin "12") (pinfunction "SDI_12") (pintype "input"))
    )
    (net (code "91") (name "Net-(U6-~{CS})") (class "Default")
      (node (ref "D7") (pin "A") (pinfunction "A_A") (pintype "passive"))
      (node (ref "R27") (pin "1") (pinfunction "1_1") (pintype "passive"))
      (node (ref "U6") (pin "9") (pinfunction "~{CS}_9") (pintype "input"))
    )
    (net (code "92") (name "Net-(U8-SCK)") (class "Default")
      (node (ref "D11") (pin "A") (pinfunction "A_A") (pintype "passive"))
      (node (ref "R31") (pin "1") (pinfunction "1_1") (pintype "passive"))
      (node (ref "U8") (pin "10") (pinfunction "SCK_10") (pintype "input"))
    )
    (net (code "93") (name "Net-(U8-SDI)") (class "Default")
      (node (ref "D12") (pin "A") (pinfunction "A_A") (pintype "passive"))
      (node (ref "R30") (pin "1") (pinfunction "1_1") (pintype "passive"))
      (node (ref "U8") (pin "12") (pinfunction "SDI_12") (pintype "input"))
    )
    (net (code "94") (name "Net-(U8-~{CS})") (class "Default")
      (node (ref "D10") (pin "A") (pinfunction "A_A") (pintype "passive"))
      (node (ref "R32") (pin "1") (pinfunction "1_1") (pintype "passive"))
      (node (ref "U8") (pin "9") (pinfunction "~{CS}_9") (pintype "input"))
    )
    (net (code "95") (name "Net-(U10-PIO2)") (class "Default")
      (node (ref "D13") (pin "A") (pinfunction "A_A") (pintype "passive"))
      (node (ref "U10") (pin "19") (pinfunction "PIO2_19") (pintype "bidirectional"))
    )
    (net (code "96") (name "Net-(U10-PIO5)") (class "Default")
      (node (ref "D14") (pin "A") (pinfunction "A_A") (pintype "passive"))
      (node (ref "U10") (pin "21") (pinfunction "PIO5_21") (pintype "bidirectional"))
    )
    (net (code "97") (name "RTS") (class "Default")
      (node (ref "SJ8") (pin "1") (pinfunction "1_1") (pintype "passive"))
      (node (ref "U10") (pin "15") (pinfunction "UARTRTS_15") (pintype "bidirectional"))
    )
    (net (code "98") (name "RX") (class "Default")
      (node (ref "U$1") (pin "14") (pinfunction "14_14") (pintype "bidirectional"))
      (node (ref "U10") (pin "13") (pinfunction "UARTRX_13") (pintype "bidirectional"))
    )
    (net (code "99") (name "TX") (class "Default")
      (node (ref "U$1") (pin "15") (pinfunction "15_15") (pintype "bidirectional"))
      (node (ref "U10") (pin "14") (pinfunction "UARTTX_14") (pintype "bidirectional"))
    )
    (net (code "100") (name "VCC") (class "Default")
      (node (ref "A0") (pin "2") (pinfunction "2_2") (pintype "passive"))
      (node (ref "A1") (pin "2") (pinfunction "2_2") (pintype "passive"))
      (node (ref "A2") (pin "1") (pinfunction "1_1") (pintype "passive"))
      (node (ref "C26") (pin "1") (pinfunction "1_1") (pintype "passive"))
      (node (ref "JP11") (pin "1") (pinfunction "1_1") (pintype "passive"))
      (node (ref "R33") (pin "2") (pinfunction "2_2") (pintype "passive"))
      (node (ref "R34") (pin "2") (pinfunction "2_2") (pintype "passive"))
      (node (ref "R35") (pin "2") (pinfunction "2_2") (pintype "passive"))
      (node (ref "U9") (pin "24") (pinfunction "VCC_24") (pintype "bidirectional"))
    )
    (net (code "101") (name "VDDIO") (class "Default")
      (node (ref "R10") (pin "1") (pinfunction "1_1") (pintype "passive"))
      (node (ref "R14") (pin "2") (pinfunction "2_2") (pintype "passive"))
      (node (ref "R6") (pin "1") (pinfunction "1_1") (pintype "passive"))
      (node (ref "R9") (pin "1") (pinfunction "1_1") (pintype "passive"))
      (node (ref "SJ7") (pin "2") (pinfunction "2_2") (pintype "passive"))
    )
    (net (code "102") (name "VIN") (class "Default")
      (node (ref "JP1") (pin "9") (pinfunction "9_9") (pintype "passive"))
      (node (ref "JP10") (pin "9") (pinfunction "9_9") (pintype "passive"))
      (node (ref "JP6") (pin "9") (pinfunction "9_9") (pintype "passive"))
      (node (ref "JP8") (pin "9") (pinfunction "9_9") (pintype "passive"))
    )
    (net (code "103") (name "unconnected-(JP2-Pad1)") (class "Default")
      (node (ref "JP2") (pin "1") (pinfunction "1_1") (pintype "passive"))
    )
    (net (code "104") (name "unconnected-(JP2-Pad2)") (class "Default")
      (node (ref "JP2") (pin "2") (pinfunction "2_2") (pintype "passive"))
    )
    (net (code "105") (name "unconnected-(JP2-Pad8)") (class "Default")
      (node (ref "JP2") (pin "8") (pinfunction "8_8") (pintype "passive"))
    )
    (net (code "106") (name "unconnected-(JP4-Pad1)") (class "Default")
      (node (ref "JP4") (pin "1") (pinfunction "1_1") (pintype "passive"))
    )
    (net (code "107") (name "unconnected-(JP4-Pad2)") (class "Default")
      (node (ref "JP4") (pin "2") (pinfunction "2_2") (pintype "passive"))
    )
    (net (code "108") (name "unconnected-(JP4-Pad4)") (class "Default")
      (node (ref "JP4") (pin "4") (pinfunction "4_4") (pintype "passive"))
    )
    (net (code "109") (name "unconnected-(JP4-Pad5)") (class "Default")
      (node (ref "JP4") (pin "5") (pinfunction "5_5") (pintype "passive"))
    )
    (net (code "110") (name "unconnected-(JP4-Pad6)") (class "Default")
      (node (ref "JP4") (pin "6") (pinfunction "6_6") (pintype "passive"))
    )
    (net (code "111") (name "unconnected-(JP4-Pad7)") (class "Default")
      (node (ref "JP4") (pin "7") (pinfunction "7_7") (pintype "passive"))
    )
    (net (code "112") (name "unconnected-(JP4-Pad8)") (class "Default")
      (node (ref "JP4") (pin "8") (pinfunction "8_8") (pintype "passive"))
    )
    (net (code "113") (name "unconnected-(U$1-GND-PadGND@1)") (class "Default")
      (node (ref "U$1") (pin "GND@1") (pinfunction "GND_GND@1") (pintype "bidirectional"))
    )
    (net (code "114") (name "unconnected-(U$1-GND-PadGND@4)") (class "Default")
      (node (ref "U$1") (pin "GND@4") (pinfunction "GND_GND@4") (pintype "bidirectional"))
    )
    (net (code "115") (name "unconnected-(U$1-GND-PadGND@5)") (class "Default")
      (node (ref "U$1") (pin "GND@5") (pinfunction "GND_GND@5") (pintype "bidirectional"))
    )
    (net (code "116") (name "unconnected-(U$1-GND-PadGND@6)") (class "Default")
      (node (ref "U$1") (pin "GND@6") (pinfunction "GND_GND@6") (pintype "bidirectional"))
    )
    (net (code "117") (name "unconnected-(U$1-GND-PadGND@7)") (class "Default")
      (node (ref "U$1") (pin "GND@7") (pinfunction "GND_GND@7") (pintype "bidirectional"))
    )
    (net (code "118") (name "unconnected-(U$1-Pad0)") (class "Default")
      (node (ref "U$1") (pin "0") (pinfunction "0_0") (pintype "bidirectional"))
    )
    (net (code "119") (name "unconnected-(U$1-Pad1)") (class "Default")
      (node (ref "U$1") (pin "1") (pinfunction "1_1") (pintype "bidirectional"))
    )
    (net (code "120") (name "unconnected-(U$1-Pad2)") (class "Default")
      (node (ref "U$1") (pin "2") (pinfunction "2_2") (pintype "bidirectional"))
    )
    (net (code "121") (name "unconnected-(U$1-Pad3)") (class "Default")
      (node (ref "U$1") (pin "3") (pinfunction "3_3") (pintype "bidirectional"))
    )
    (net (code "122") (name "unconnected-(U$1-Pad4)") (class "Default")
      (node (ref "U$1") (pin "4") (pinfunction "4_4") (pintype "bidirectional"))
    )
    (net (code "123") (name "unconnected-(U$1-Pad5)") (class "Default")
      (node (ref "U$1") (pin "5") (pinfunction "5_5") (pintype "bidirectional"))
    )
    (net (code "124") (name "unconnected-(U$1-Pad6)") (class "Default")
      (node (ref "U$1") (pin "6") (pinfunction "6_6") (pintype "bidirectional"))
    )
    (net (code "125") (name "unconnected-(U$1-Pad7)") (class "Default")
      (node (ref "U$1") (pin "7") (pinfunction "7_7") (pintype "bidirectional"))
    )
    (net (code "126") (name "unconnected-(U$1-Pad8)") (class "Default")
      (node (ref "U$1") (pin "8") (pinfunction "8_8") (pintype "bidirectional"))
    )
    (net (code "127") (name "unconnected-(U$1-Pad9)") (class "Default")
      (node (ref "U$1") (pin "9") (pinfunction "9_9") (pintype "bidirectional"))
    )
    (net (code "128") (name "unconnected-(U$1-Pad10)") (class "Default")
      (node (ref "U$1") (pin "10") (pinfunction "10_10") (pintype "bidirectional"))
    )
    (net (code "129") (name "unconnected-(U$1-Pad11)") (class "Default")
      (node (ref "U$1") (pin "11") (pinfunction "11_11") (pintype "bidirectional"))
    )
    (net (code "130") (name "unconnected-(U$1-Pad12)") (class "Default")
      (node (ref "U$1") (pin "12") (pinfunction "12_12") (pintype "bidirectional"))
    )
    (net (code "131") (name "unconnected-(U$1-Pad13)") (class "Default")
      (node (ref "U$1") (pin "13") (pinfunction "13_13") (pintype "bidirectional"))
    )
    (net (code "132") (name "unconnected-(U$1-Pad16)") (class "Default")
      (node (ref "U$1") (pin "16") (pinfunction "16_16") (pintype "bidirectional"))
    )
    (net (code "133") (name "unconnected-(U$1-Pad17)") (class "Default")
      (node (ref "U$1") (pin "17") (pinfunction "17_17") (pintype "bidirectional"))
    )
    (net (code "134") (name "unconnected-(U$1-Pad18)") (class "Default")
      (node (ref "U$1") (pin "18") (pinfunction "18_18") (pintype "bidirectional"))
    )
    (net (code "135") (name "unconnected-(U$1-Pad19)") (class "Default")
      (node (ref "U$1") (pin "19") (pinfunction "19_19") (pintype "bidirectional"))
    )
    (net (code "136") (name "unconnected-(U$1-Pad22)") (class "Default")
      (node (ref "U$1") (pin "22") (pinfunction "22_22") (pintype "bidirectional"))
    )
    (net (code "137") (name "unconnected-(U$1-Pad23)") (class "Default")
      (node (ref "U$1") (pin "23") (pinfunction "23_23") (pintype "bidirectional"))
    )
    (net (code "138") (name "unconnected-(U$1-Pad24)") (class "Default")
      (node (ref "U$1") (pin "24") (pinfunction "24_24") (pintype "bidirectional"))
    )
    (net (code "139") (name "unconnected-(U$1-Pad25)") (class "Default")
      (node (ref "U$1") (pin "25") (pinfunction "25_25") (pintype "bidirectional"))
    )
    (net (code "140") (name "unconnected-(U$1-Pad26)") (class "Default")
      (node (ref "U$1") (pin "26") (pinfunction "26_26") (pintype "bidirectional"))
    )
    (net (code "141") (name "unconnected-(U$1-Pad27)") (class "Default")
      (node (ref "U$1") (pin "27") (pinfunction "27_27") (pintype "bidirectional"))
    )
    (net (code "142") (name "unconnected-(U$1-Pad28)") (class "Default")
      (node (ref "U$1") (pin "28") (pinfunction "28_28") (pintype "bidirectional"))
    )
    (net (code "143") (name "unconnected-(U$1-Pad29)") (class "Default")
      (node (ref "U$1") (pin "29") (pinfunction "29_29") (pintype "bidirectional"))
    )
    (net (code "144") (name "unconnected-(U$1-Pad30)") (class "Default")
      (node (ref "U$1") (pin "30") (pinfunction "30_30") (pintype "bidirectional"))
    )
    (net (code "145") (name "unconnected-(U$1-Pad31)") (class "Default")
      (node (ref "U$1") (pin "31") (pinfunction "31_31") (pintype "bidirectional"))
    )
    (net (code "146") (name "unconnected-(U$1-Pad32)") (class "Default")
      (node (ref "U$1") (pin "32") (pinfunction "32_32") (pintype "bidirectional"))
    )
    (net (code "147") (name "unconnected-(U$1-Pad33)") (class "Default")
      (node (ref "U$1") (pin "33") (pinfunction "33_33") (pintype "bidirectional"))
    )
    (net (code "148") (name "unconnected-(U$1-Pad34)") (class "Default")
      (node (ref "U$1") (pin "34") (pinfunction "34_34") (pintype "bidirectional"))
    )
    (net (code "149") (name "unconnected-(U$1-Pad35)") (class "Default")
      (node (ref "U$1") (pin "35") (pinfunction "35_35") (pintype "bidirectional"))
    )
    (net (code "150") (name "unconnected-(U$1-Pad36)") (class "Default")
      (node (ref "U$1") (pin "36") (pinfunction "36_36") (pintype "bidirectional"))
    )
    (net (code "151") (name "unconnected-(U$1-Pad37)") (class "Default")
      (node (ref "U$1") (pin "37") (pinfunction "37_37") (pintype "bidirectional"))
    )
    (net (code "152") (name "unconnected-(U$1-Pad38)") (class "Default")
      (node (ref "U$1") (pin "38") (pinfunction "38_38") (pintype "bidirectional"))
    )
    (net (code "153") (name "unconnected-(U$1-Pad39)") (class "Default")
      (node (ref "U$1") (pin "39") (pinfunction "39_39") (pintype "bidirectional"))
    )
    (net (code "154") (name "unconnected-(U$1-Pad40)") (class "Default")
      (node (ref "U$1") (pin "40") (pinfunction "40_40") (pintype "bidirectional"))
    )
    (net (code "155") (name "unconnected-(U$1-Pad41)") (class "Default")
      (node (ref "U$1") (pin "41") (pinfunction "41_41") (pintype "bidirectional"))
    )
    (net (code "156") (name "unconnected-(U$1-Pad42)") (class "Default")
      (node (ref "U$1") (pin "42") (pinfunction "42_42") (pintype "bidirectional"))
    )
    (net (code "157") (name "unconnected-(U$1-Pad43)") (class "Default")
      (node (ref "U$1") (pin "43") (pinfunction "43_43") (pintype "bidirectional"))
    )
    (net (code "158") (name "unconnected-(U$1-Pad44)") (class "Default")
      (node (ref "U$1") (pin "44") (pinfunction "44_44") (pintype "bidirectional"))
    )
    (net (code "159") (name "unconnected-(U$1-Pad45)") (class "Default")
      (node (ref "U$1") (pin "45") (pinfunction "45_45") (pintype "bidirectional"))
    )
    (net (code "160") (name "unconnected-(U$1-Pad46)") (class "Default")
      (node (ref "U$1") (pin "46") (pinfunction "46_46") (pintype "bidirectional"))
    )
    (net (code "161") (name "unconnected-(U$1-Pad47)") (class "Default")
      (node (ref "U$1") (pin "47") (pinfunction "47_47") (pintype "bidirectional"))
    )
    (net (code "162") (name "unconnected-(U$1-Pad48)") (class "Default")
      (node (ref "U$1") (pin "48") (pinfunction "48_48") (pintype "bidirectional"))
    )
    (net (code "163") (name "unconnected-(U$1-Pad49)") (class "Default")
      (node (ref "U$1") (pin "49") (pinfunction "49_49") (pintype "bidirectional"))
    )
    (net (code "164") (name "unconnected-(U$1-PadA6)") (class "Default")
      (node (ref "U$1") (pin "A6") (pinfunction "A6_A6") (pintype "bidirectional"))
    )
    (net (code "165") (name "unconnected-(U$1-PadA7)") (class "Default")
      (node (ref "U$1") (pin "A7") (pinfunction "A7_A7") (pintype "bidirectional"))
    )
    (net (code "166") (name "unconnected-(U$1-PadA8)") (class "Default")
      (node (ref "U$1") (pin "A8") (pinfunction "A8_A8") (pintype "bidirectional"))
    )
    (net (code "167") (name "unconnected-(U$1-PadA9)") (class "Default")
      (node (ref "U$1") (pin "A9") (pinfunction "A9_A9") (pintype "bidirectional"))
    )
    (net (code "168") (name "unconnected-(U$1-PadA10)") (class "Default")
      (node (ref "U$1") (pin "A10") (pinfunction "A10_A10") (pintype "bidirectional"))
    )
    (net (code "169") (name "unconnected-(U$1-PadA11)") (class "Default")
      (node (ref "U$1") (pin "A11") (pinfunction "A11_A11") (pintype "bidirectional"))
    )
    (net (code "170") (name "unconnected-(U$1-PadA12)") (class "Default")
      (node (ref "U$1") (pin "A12") (pinfunction "A12_A12") (pintype "bidirectional"))
    )
    (net (code "171") (name "unconnected-(U$1-PadA13)") (class "Default")
      (node (ref "U$1") (pin "A13") (pinfunction "A13_A13") (pintype "bidirectional"))
    )
    (net (code "172") (name "unconnected-(U$1-PadA14)") (class "Default")
      (node (ref "U$1") (pin "A14") (pinfunction "A14_A14") (pintype "bidirectional"))
    )
    (net (code "173") (name "unconnected-(U$1-PadA15)") (class "Default")
      (node (ref "U$1") (pin "A15") (pinfunction "A15_A15") (pintype "bidirectional"))
    )
    (net (code "174") (name "unconnected-(U$1-PadAREF)") (class "Default")
      (node (ref "U$1") (pin "AREF") (pinfunction "AREF_AREF") (pintype "bidirectional"))
    )
    (net (code "175") (name "unconnected-(U$14-DAT1-Pad8)") (class "Default")
      (node (ref "U$14") (pin "8") (pinfunction "DAT1_8") (pintype "bidirectional"))
    )
    (net (code "176") (name "unconnected-(U$14-DAT2-Pad9)") (class "Default")
      (node (ref "U$14") (pin "9") (pinfunction "DAT2_9") (pintype "bidirectional"))
    )
    (net (code "177") (name "unconnected-(U1-DNC-Pad6)") (class "Default")
      (node (ref "U1") (pin "6") (pinfunction "DNC_6") (pintype "no_connect"))
    )
    (net (code "178") (name "unconnected-(U2-DNC-Pad6)") (class "Default")
      (node (ref "U2") (pin "6") (pinfunction "DNC_6") (pintype "no_connect"))
    )
    (net (code "179") (name "unconnected-(U3-P4-Pad4)") (class "Default")
      (node (ref "U3") (pin "4") (pinfunction "P4_4") (pintype "bidirectional"))
    )
    (net (code "180") (name "unconnected-(U4-2A-Pad5)") (class "Default")
      (node (ref "U4") (pin "5") (pinfunction "2A_5") (pintype "bidirectional"))
    )
    (net (code "181") (name "unconnected-(U4-2Y-Pad4)") (class "Default")
      (node (ref "U4") (pin "4") (pinfunction "2Y_4") (pintype "bidirectional"))
    )
    (net (code "182") (name "unconnected-(U4-5A-Pad11)") (class "Default")
      (node (ref "U4") (pin "11") (pinfunction "5A_11") (pintype "bidirectional"))
    )
    (net (code "183") (name "unconnected-(U4-5Y-Pad12)") (class "Default")
      (node (ref "U4") (pin "12") (pinfunction "5Y_12") (pintype "bidirectional"))
    )
    (net (code "184") (name "unconnected-(U4-6A-Pad14)") (class "Default")
      (node (ref "U4") (pin "14") (pinfunction "6A_14") (pintype "bidirectional"))
    )
    (net (code "185") (name "unconnected-(U4-6Y-Pad15)") (class "Default")
      (node (ref "U4") (pin "15") (pinfunction "6Y_15") (pintype "bidirectional"))
    )
    (net (code "186") (name "unconnected-(U6-DNC-Pad6)") (class "Default")
      (node (ref "U6") (pin "6") (pinfunction "DNC_6") (pintype "no_connect"))
    )
    (net (code "187") (name "unconnected-(U8-DNC-Pad6)") (class "Default")
      (node (ref "U8") (pin "6") (pinfunction "DNC_6") (pintype "no_connect"))
    )
    (net (code "188") (name "unconnected-(U10-AIO0-Pad30)") (class "Default")
      (node (ref "U10") (pin "30") (pinfunction "AIO0_30") (pintype "bidirectional"))
    )
    (net (code "189") (name "unconnected-(U10-AIO1-Pad35)") (class "Default")
      (node (ref "U10") (pin "35") (pinfunction "AIO1_35") (pintype "bidirectional"))
    )
    (net (code "190") (name "unconnected-(U10-PCMCLK-Pad7)") (class "Default")
      (node (ref "U10") (pin "7") (pinfunction "PCMCLK_7") (pintype "bidirectional"))
    )
    (net (code "191") (name "unconnected-(U10-PCMIN-Pad9)") (class "Default")
      (node (ref "U10") (pin "9") (pinfunction "PCMIN_9") (pintype "bidirectional"))
    )
    (net (code "192") (name "unconnected-(U10-PCMOUT-Pad10)") (class "Default")
      (node (ref "U10") (pin "10") (pinfunction "PCMOUT_10") (pintype "bidirectional"))
    )
    (net (code "193") (name "unconnected-(U10-PCMSYNC-Pad8)") (class "Default")
      (node (ref "U10") (pin "8") (pinfunction "PCMSYNC_8") (pintype "bidirectional"))
    )
    (net (code "194") (name "unconnected-(U10-PIO3-Pad20)") (class "Default")
      (node (ref "U10") (pin "20") (pinfunction "PIO3_20") (pintype "bidirectional"))
    )
    (net (code "195") (name "unconnected-(U10-PIO6-Pad3)") (class "Default")
      (node (ref "U10") (pin "3") (pinfunction "PIO6_3") (pintype "bidirectional"))
    )
    (net (code "196") (name "unconnected-(U10-PIO7-Pad4)") (class "Default")
      (node (ref "U10") (pin "4") (pinfunction "PIO7_4") (pintype "bidirectional"))
    )
    (net (code "197") (name "unconnected-(U10-PIO8-Pad31)") (class "Default")
      (node (ref "U10") (pin "31") (pinfunction "PIO8_31") (pintype "bidirectional"))
    )
    (net (code "198") (name "unconnected-(U10-PIO9-Pad32)") (class "Default")
      (node (ref "U10") (pin "32") (pinfunction "PIO9_32") (pintype "bidirectional"))
    )
    (net (code "199") (name "unconnected-(U10-PIO10-Pad33)") (class "Default")
      (node (ref "U10") (pin "33") (pinfunction "PIO10_33") (pintype "bidirectional"))
    )
    (net (code "200") (name "unconnected-(U10-PIO11-Pad34)") (class "Default")
      (node (ref "U10") (pin "34") (pinfunction "PIO11_34") (pintype "bidirectional"))
    )
    (net (code "201") (name "unconnected-(U10-RESET-Pad5)") (class "Default")
      (node (ref "U10") (pin "5") (pinfunction "RESET_5") (pintype "bidirectional"))
    )
    (net (code "202") (name "unconnected-(U10-SPICLK-Pad6)") (class "Default")
      (node (ref "U10") (pin "6") (pinfunction "SPICLK_6") (pintype "bidirectional"))
    )
    (net (code "203") (name "unconnected-(U10-SPICSB-Pad23)") (class "Default")
      (node (ref "U10") (pin "23") (pinfunction "SPICSB_23") (pintype "bidirectional"))
    )
    (net (code "204") (name "unconnected-(U10-SPIMISO-Pad24)") (class "Default")
      (node (ref "U10") (pin "24") (pinfunction "SPIMISO_24") (pintype "bidirectional"))
    )
    (net (code "205") (name "unconnected-(U10-SPIMOSI-Pad2)") (class "Default")
      (node (ref "U10") (pin "2") (pinfunction "SPIMOSI_2") (pintype "bidirectional"))
    )
    (net (code "206") (name "unconnected-(U10-USBD+-Pad17)") (class "Default")
      (node (ref "U10") (pin "17") (pinfunction "USBD+_17") (pintype "bidirectional"))
    )
    (net (code "207") (name "unconnected-(U10-USBD--Pad18)") (class "Default")
      (node (ref "U10") (pin "18") (pinfunction "USBD-_18") (pintype "bidirectional"))
    )
    (net (code "208") (name "unconnected-(U12-PadNULL)") (class "Default")
      (node (ref "U12") (pin "NULL") (pinfunction "NULL_NULL") (pintype "no_connect"))
    )
  )
)
